# Replicape_B2.net
KiCad netlist of a schematic drawn in EAGLE
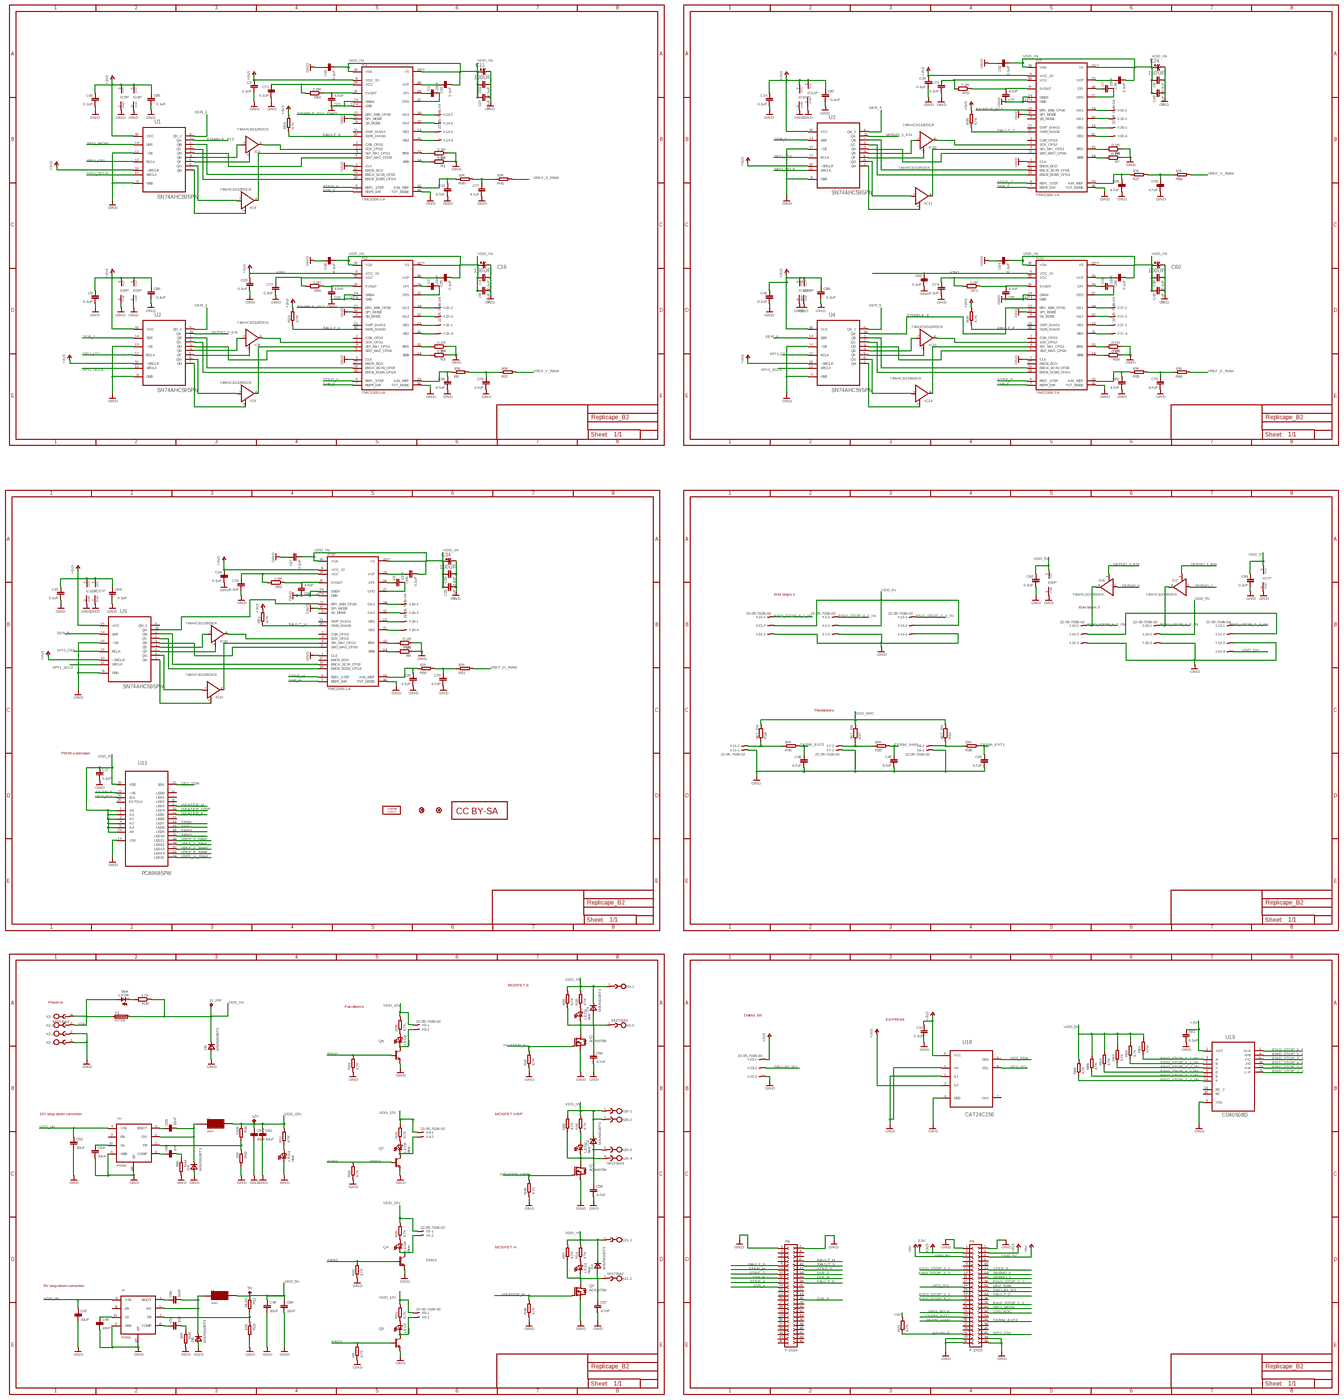
[diagram p0: schematic, sheet 1, overview]
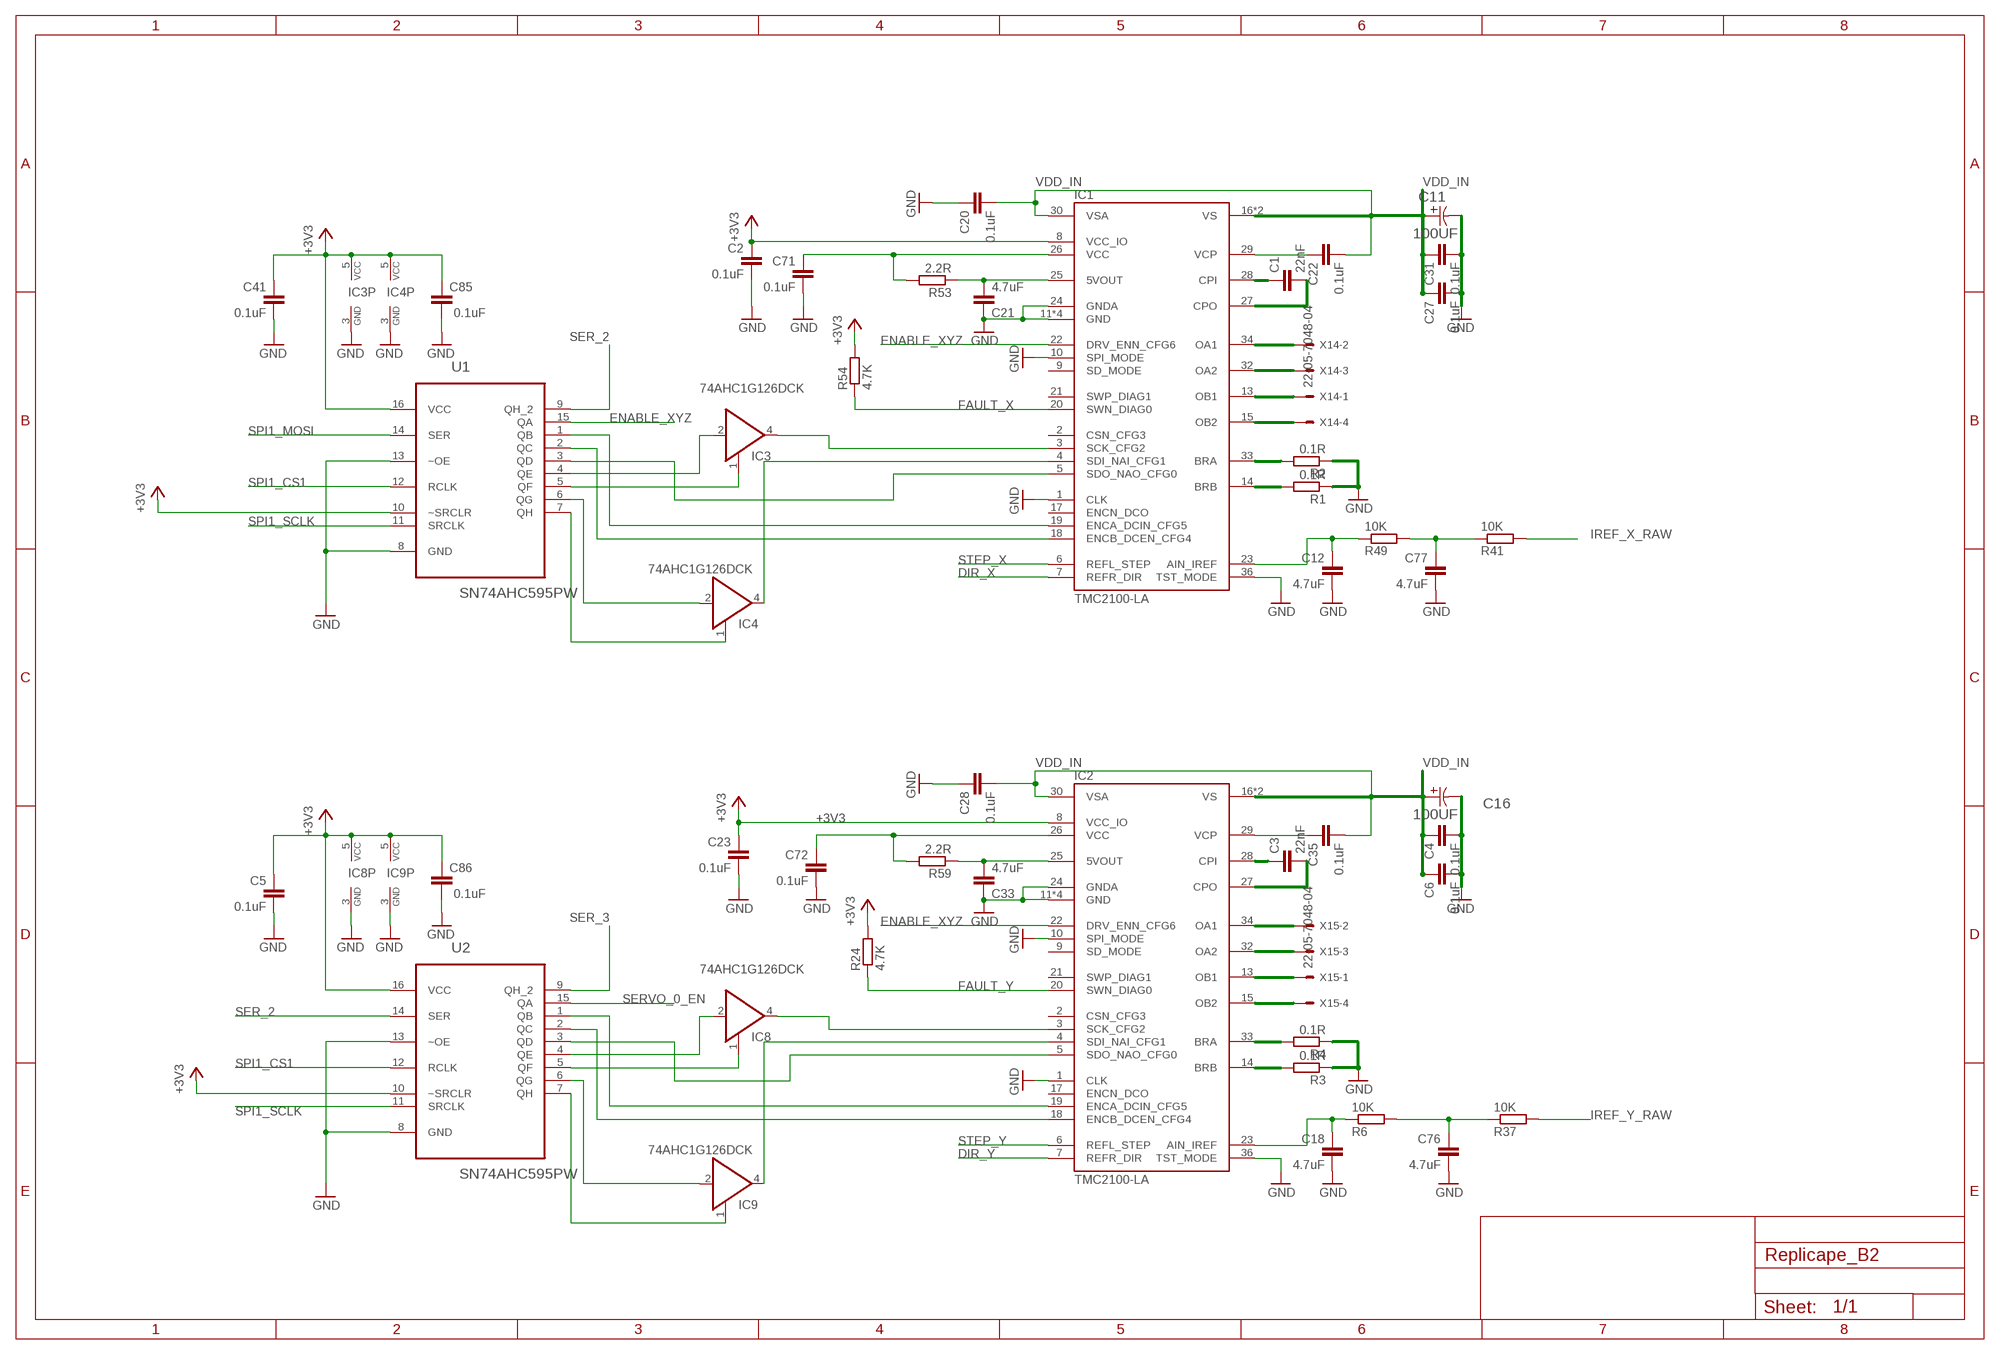
[diagram p1: schematic, sheet 1, part 1 of 4]
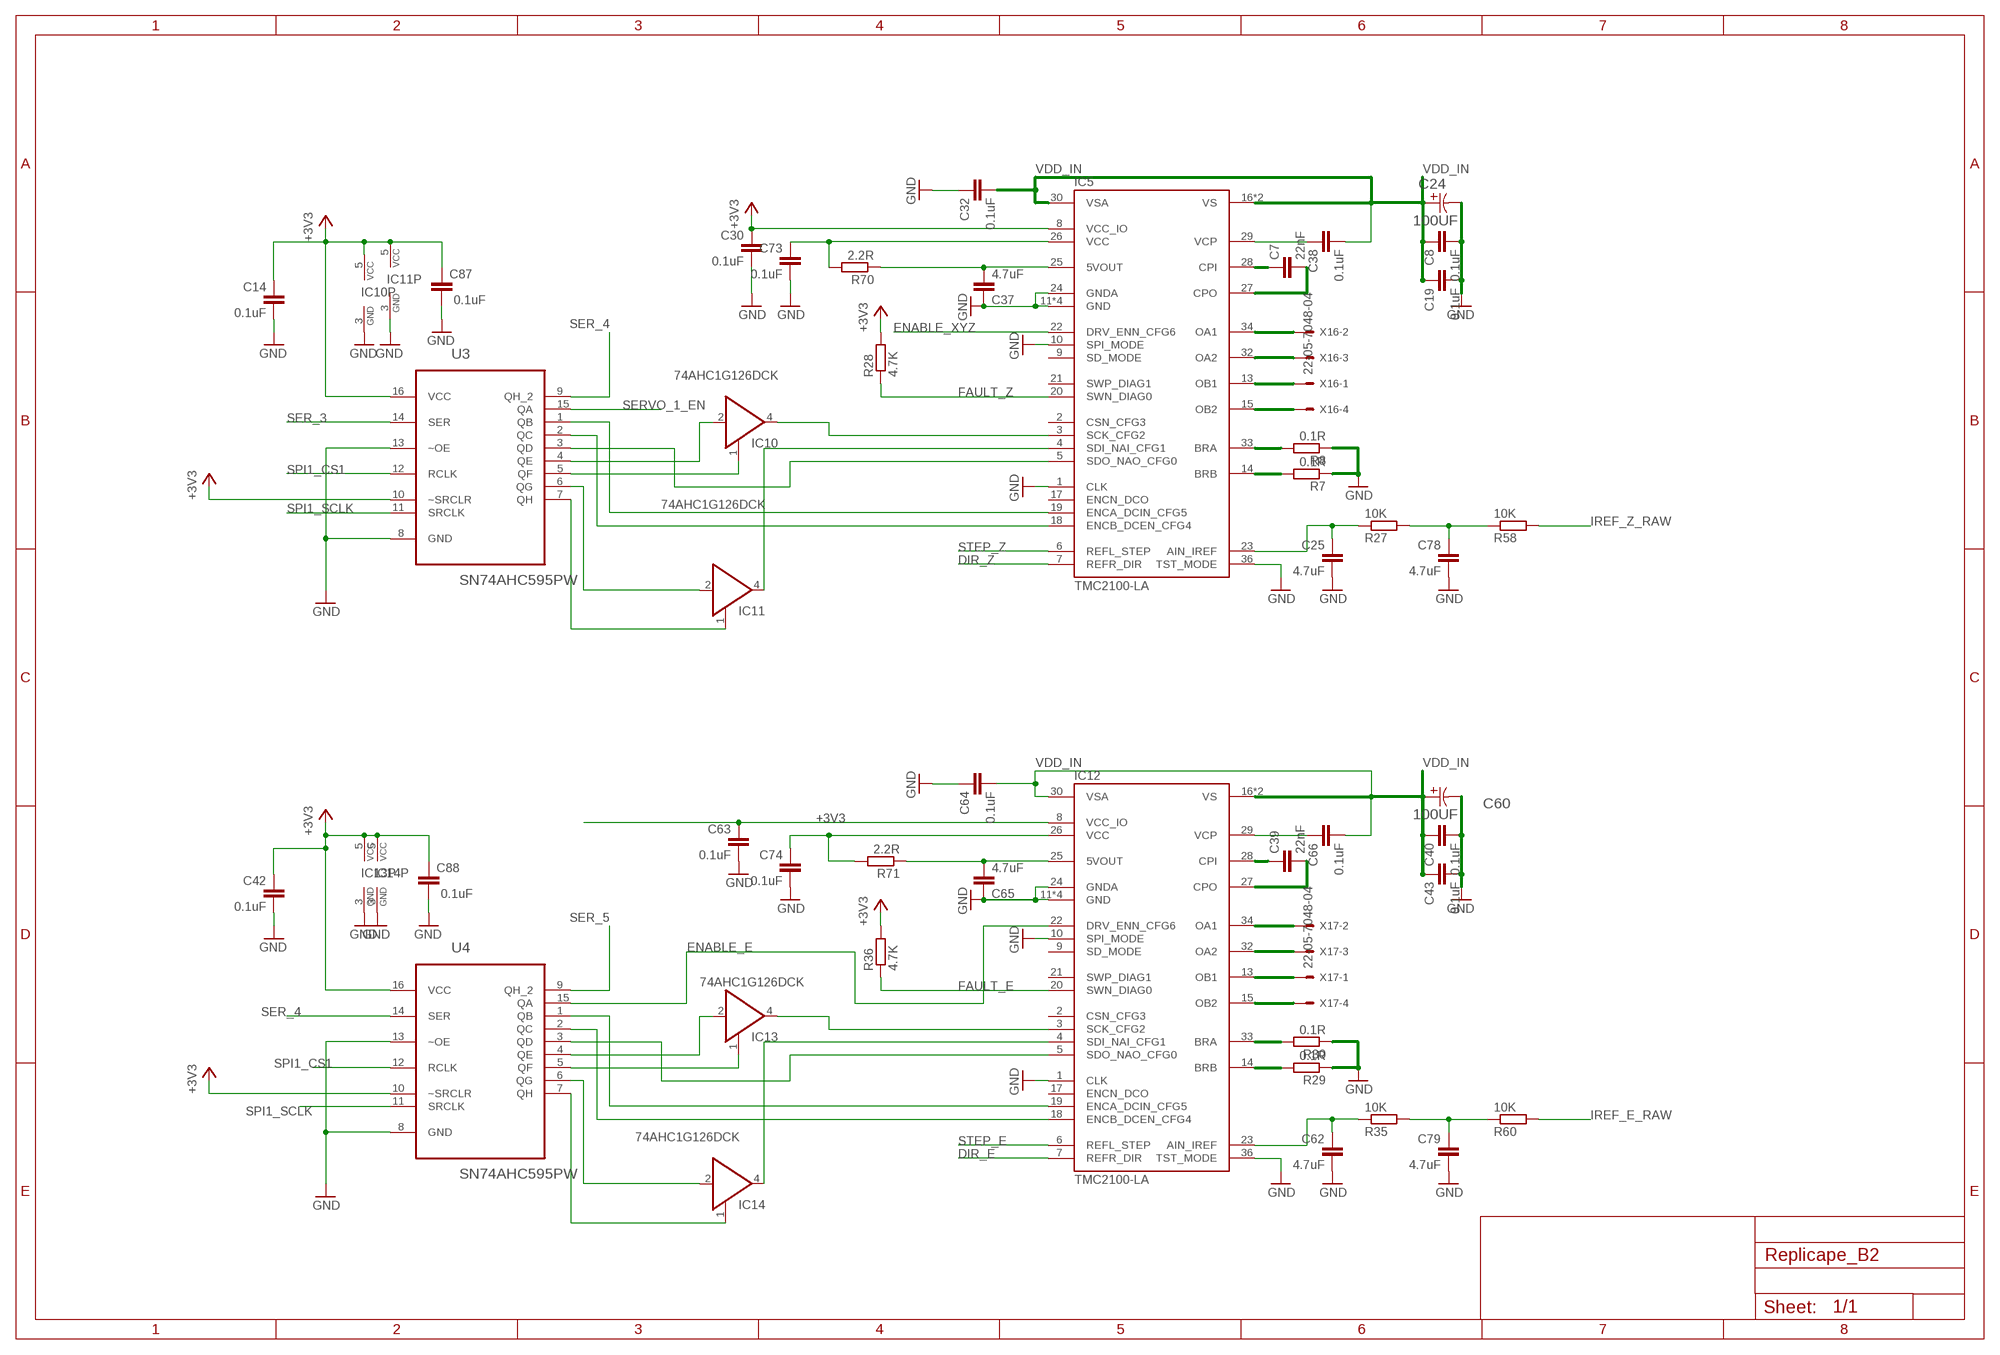
[diagram p2: schematic, sheet 1, part 2 of 4]
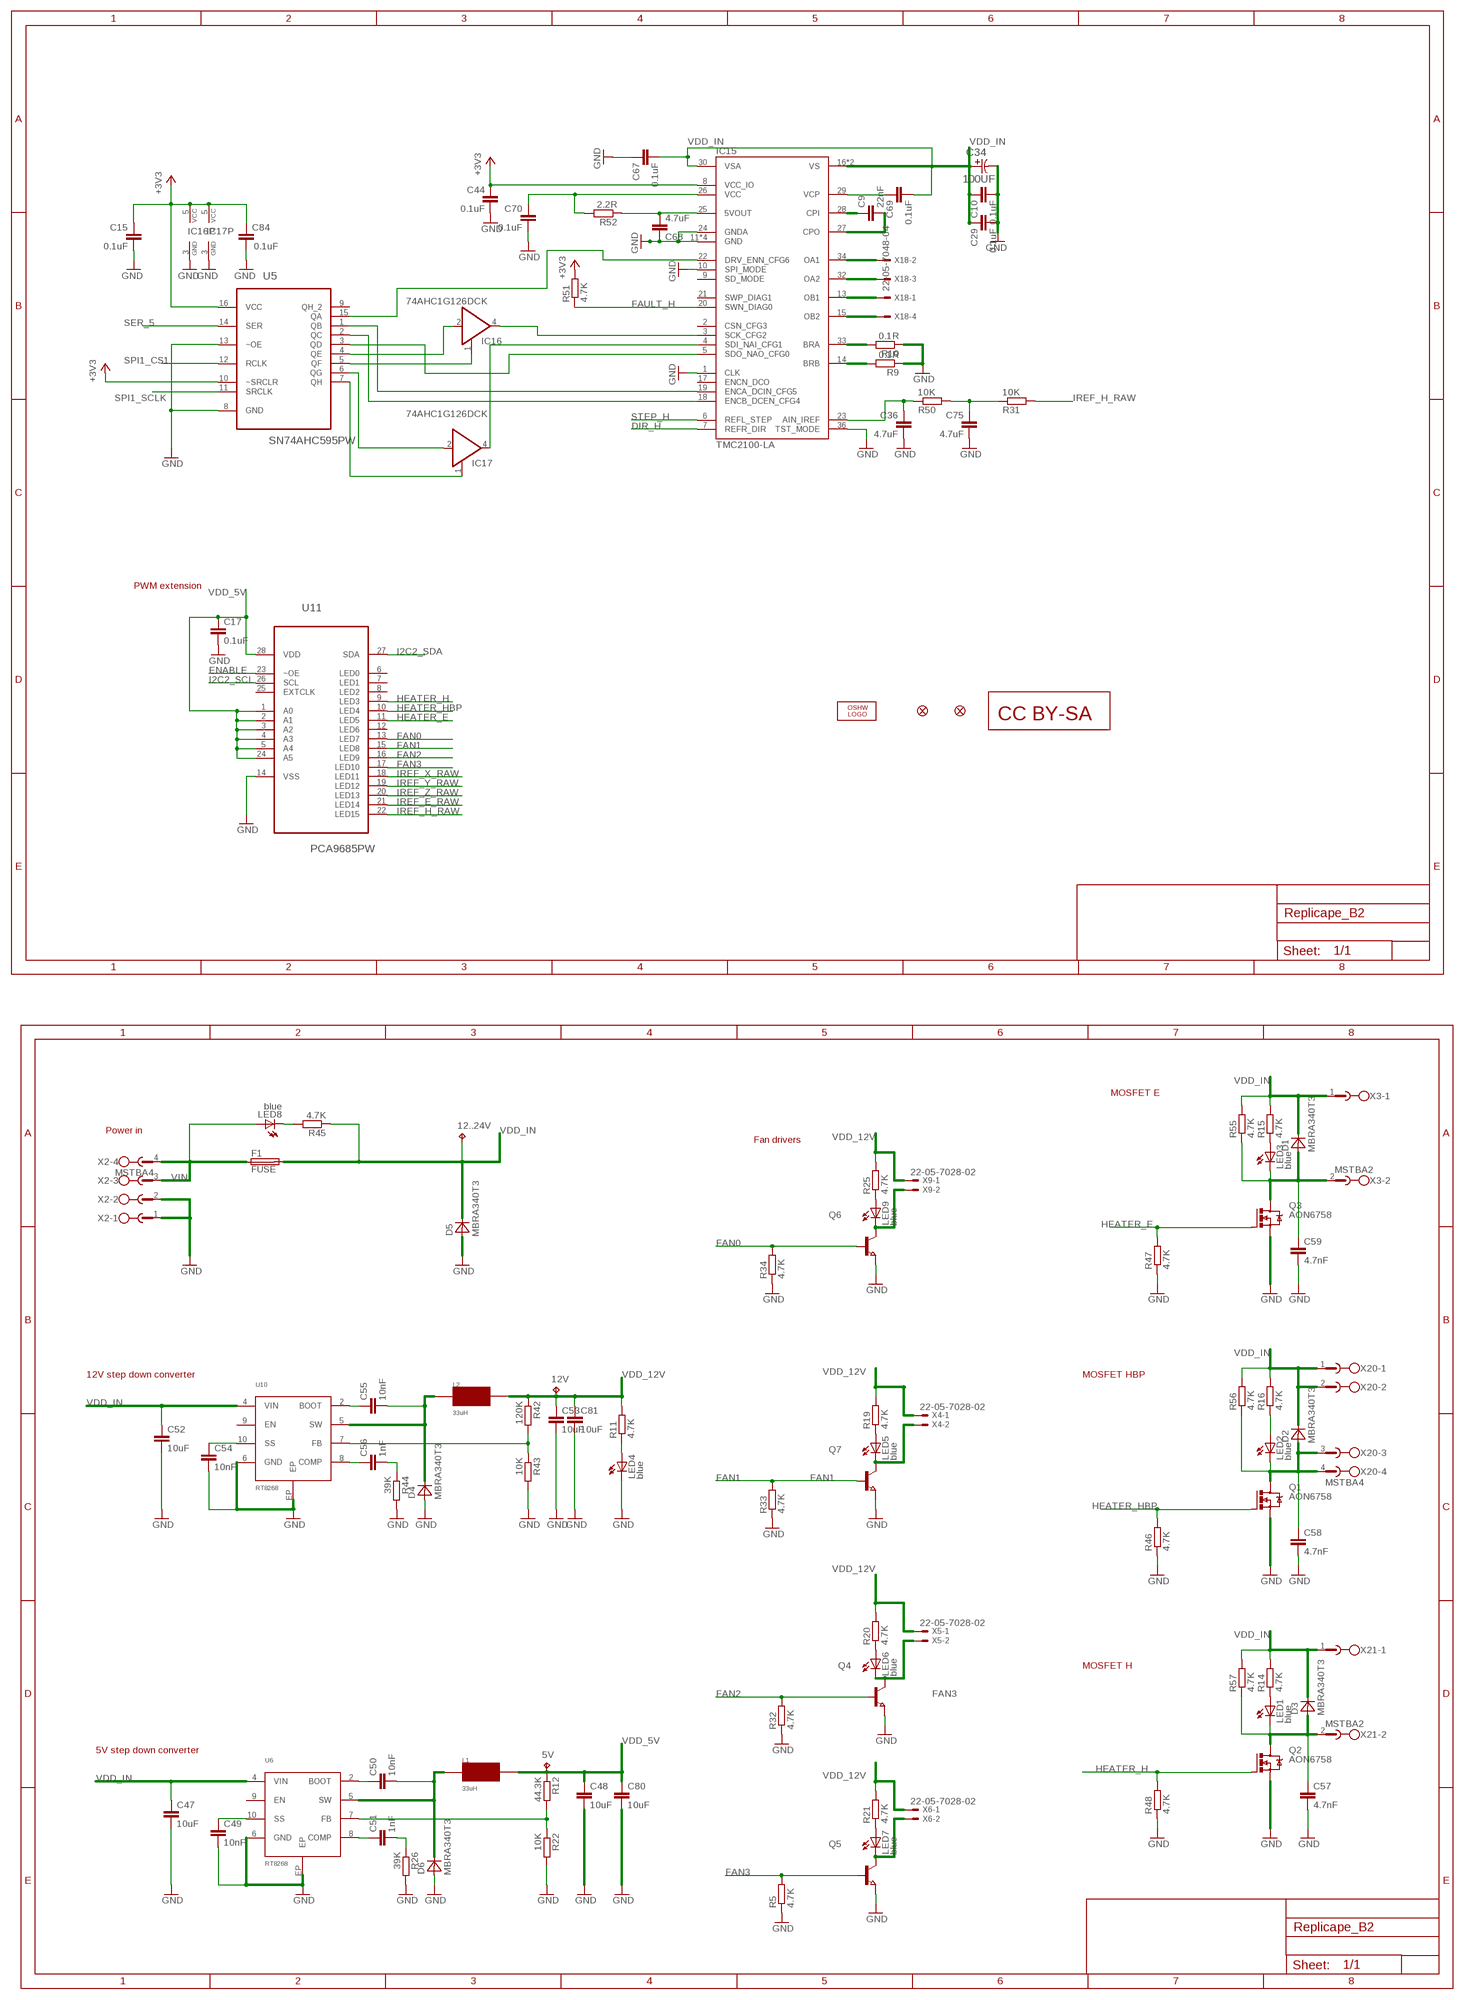
[diagram p3: schematic, sheet 1, part 3 of 4]
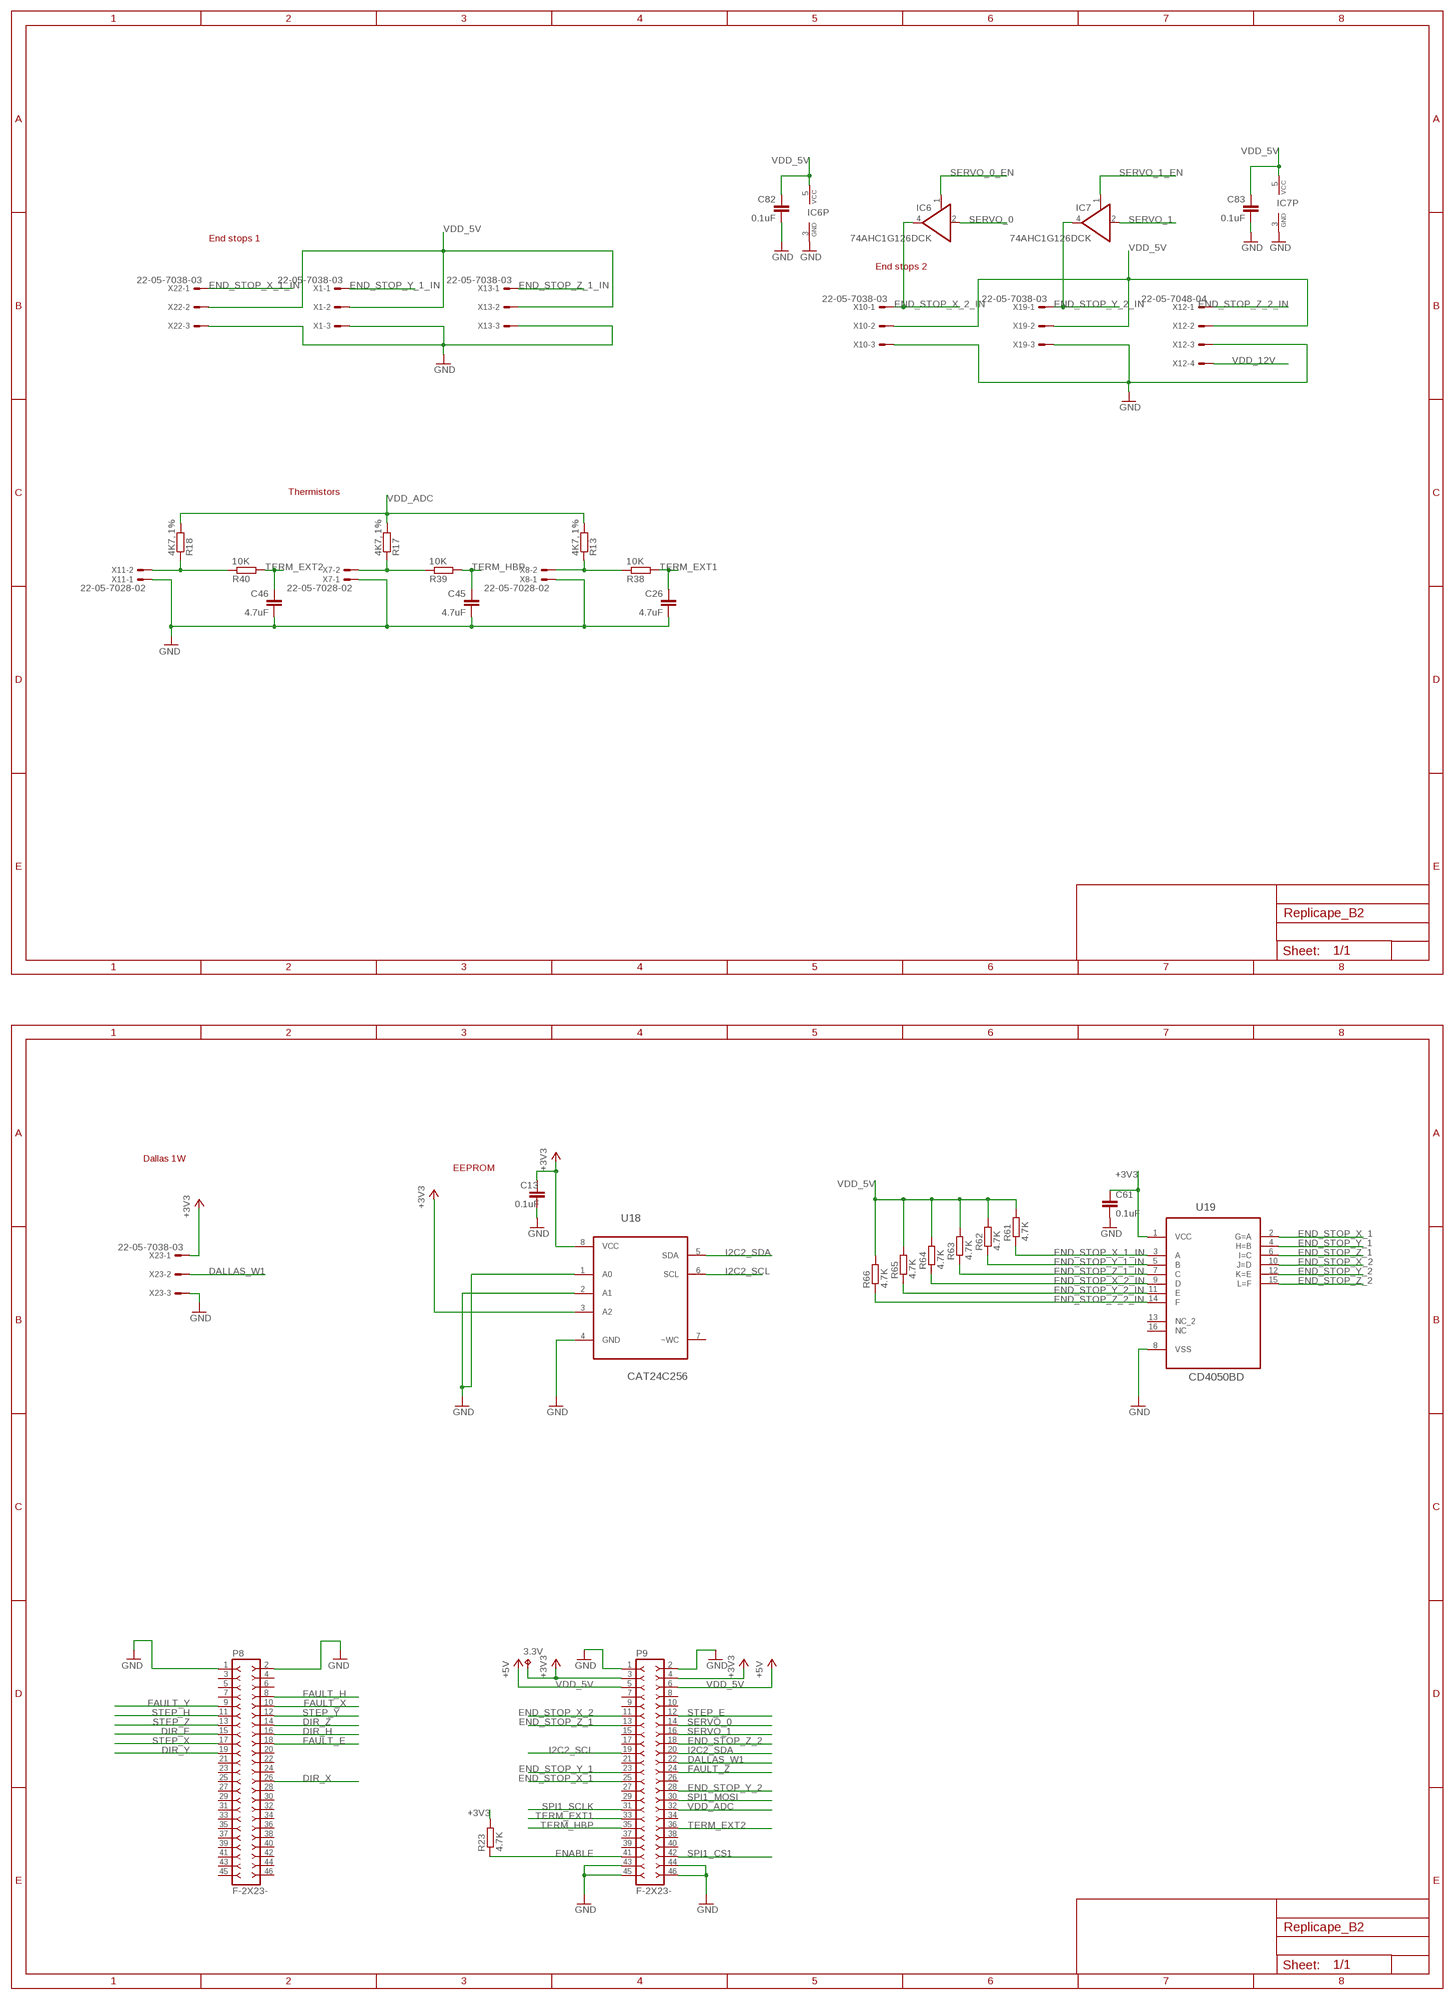
[diagram p4: schematic, sheet 1, part 4 of 4]

(export (version "E")
  (design (tool "Eeschema 10.0.6"))
  (components
    (comp (ref "3.3V")
      (value "TPB1,27")
      (footprint "eagle-import:B1,27")
      (libsource (lib "eagle-import") (part "TPB1,27"))
    )
    (comp (ref "5V")
      (value "TPB1,27")
      (footprint "eagle-import:B1,27")
      (libsource (lib "eagle-import") (part "TPB1,27"))
    )
    (comp (ref "12..24V")
      (value "TPB1,27")
      (footprint "eagle-import:B1,27")
      (libsource (lib "eagle-import") (part "TPB1,27"))
    )
    (comp (ref "12V")
      (value "TPB1,27")
      (footprint "eagle-import:B1,27")
      (libsource (lib "eagle-import") (part "TPB1,27"))
    )
    (comp (ref "C1")
      (value "22nF")
      (footprint "eagle-import:C0402")
      (libsource (lib "eagle-import") (part "C-EUC0402"))
    )
    (comp (ref "C2")
      (value "0.1uF")
      (footprint "eagle-import:C0402")
      (libsource (lib "eagle-import") (part "C-EUC0402"))
    )
    (comp (ref "C3")
      (value "22nF")
      (footprint "eagle-import:C0402")
      (libsource (lib "eagle-import") (part "C-EUC0402"))
    )
    (comp (ref "C4")
      (value "0.1uF")
      (footprint "eagle-import:C0402")
      (libsource (lib "eagle-import") (part "C-EUC0402"))
    )
    (comp (ref "C5")
      (value "0.1uF")
      (footprint "eagle-import:C0402")
      (libsource (lib "eagle-import") (part "C-EUC0402"))
    )
    (comp (ref "C6")
      (value "0.1uF")
      (footprint "eagle-import:C0402")
      (libsource (lib "eagle-import") (part "C-EUC0402"))
    )
    (comp (ref "C7")
      (value "22nF")
      (footprint "eagle-import:C0402")
      (libsource (lib "eagle-import") (part "C-EUC0402"))
    )
    (comp (ref "C8")
      (value "0.1uF")
      (footprint "eagle-import:C0402")
      (libsource (lib "eagle-import") (part "C-EUC0402"))
    )
    (comp (ref "C9")
      (value "22nF")
      (footprint "eagle-import:C0402")
      (libsource (lib "eagle-import") (part "C-EUC0402"))
    )
    (comp (ref "C10")
      (value "0.1uF")
      (footprint "eagle-import:C0402")
      (libsource (lib "eagle-import") (part "C-EUC0402"))
    )
    (comp (ref "C11")
      (value "100UF")
      (footprint "eagle-import:CAPAE660X800N")
      (fields (field (name "MPN") "EEE-FK1V101XP") (field (name "TOLERANCE") "±20 %"))
      (libsource (lib "eagle-import") (part "EEE--CASE-D8FK1V101XP"))
    )
    (comp (ref "C12")
      (value "4.7uF")
      (footprint "eagle-import:C0402")
      (libsource (lib "eagle-import") (part "C-EUC0402"))
    )
    (comp (ref "C13")
      (value "0.1uF")
      (footprint "eagle-import:C0402")
      (libsource (lib "eagle-import") (part "C-EUC0402"))
    )
    (comp (ref "C14")
      (value "0.1uF")
      (footprint "eagle-import:C0402")
      (libsource (lib "eagle-import") (part "C-EUC0402"))
    )
    (comp (ref "C15")
      (value "0.1uF")
      (footprint "eagle-import:C0402")
      (libsource (lib "eagle-import") (part "C-EUC0402"))
    )
    (comp (ref "C16")
      (value "100UF")
      (footprint "eagle-import:CAPAE660X800N")
      (fields (field (name "MPN") "EEE-FK1V101XP") (field (name "TOLERANCE") "±20 %"))
      (libsource (lib "eagle-import") (part "EEE--CASE-D8FK1V101XP"))
    )
    (comp (ref "C17")
      (value "0.1uF")
      (footprint "eagle-import:C0402")
      (libsource (lib "eagle-import") (part "C-EUC0402"))
    )
    (comp (ref "C18")
      (value "4.7uF")
      (footprint "eagle-import:C0402")
      (libsource (lib "eagle-import") (part "C-EUC0402"))
    )
    (comp (ref "C19")
      (value "0.1uF")
      (footprint "eagle-import:C0402")
      (libsource (lib "eagle-import") (part "C-EUC0402"))
    )
    (comp (ref "C20")
      (value "0.1uF")
      (footprint "eagle-import:C0402")
      (libsource (lib "eagle-import") (part "C-EUC0402"))
    )
    (comp (ref "C21")
      (value "4.7uF")
      (footprint "eagle-import:C0402")
      (libsource (lib "eagle-import") (part "C-EUC0402"))
    )
    (comp (ref "C22")
      (value "0.1uF")
      (footprint "eagle-import:C0402")
      (libsource (lib "eagle-import") (part "C-EUC0402"))
    )
    (comp (ref "C23")
      (value "0.1uF")
      (footprint "eagle-import:C0402")
      (libsource (lib "eagle-import") (part "C-EUC0402"))
    )
    (comp (ref "C24")
      (value "100UF")
      (footprint "eagle-import:CAPAE660X800N")
      (fields (field (name "MPN") "EEE-FK1V101XP") (field (name "TOLERANCE") "±20 %"))
      (libsource (lib "eagle-import") (part "EEE--CASE-D8FK1V101XP"))
    )
    (comp (ref "C25")
      (value "4.7uF")
      (footprint "eagle-import:C0402")
      (libsource (lib "eagle-import") (part "C-EUC0402"))
    )
    (comp (ref "C26")
      (value "4.7uF")
      (footprint "eagle-import:C0402")
      (libsource (lib "eagle-import") (part "C-EUC0402"))
    )
    (comp (ref "C27")
      (value "0.1uF")
      (footprint "eagle-import:C0402")
      (libsource (lib "eagle-import") (part "C-EUC0402"))
    )
    (comp (ref "C28")
      (value "0.1uF")
      (footprint "eagle-import:C0402")
      (libsource (lib "eagle-import") (part "C-EUC0402"))
    )
    (comp (ref "C29")
      (value "0.1uF")
      (footprint "eagle-import:C0402")
      (libsource (lib "eagle-import") (part "C-EUC0402"))
    )
    (comp (ref "C30")
      (value "0.1uF")
      (footprint "eagle-import:C0402")
      (libsource (lib "eagle-import") (part "C-EUC0402"))
    )
    (comp (ref "C31")
      (value "0.1uF")
      (footprint "eagle-import:C0402")
      (libsource (lib "eagle-import") (part "C-EUC0402"))
    )
    (comp (ref "C32")
      (value "0.1uF")
      (footprint "eagle-import:C0402")
      (libsource (lib "eagle-import") (part "C-EUC0402"))
    )
    (comp (ref "C33")
      (value "4.7uF")
      (footprint "eagle-import:C0402")
      (libsource (lib "eagle-import") (part "C-EUC0402"))
    )
    (comp (ref "C34")
      (value "100UF")
      (footprint "eagle-import:CAPAE660X800N")
      (fields (field (name "MPN") "EEE-FK1V101XP") (field (name "TOLERANCE") "±20 %"))
      (libsource (lib "eagle-import") (part "EEE--CASE-D8FK1V101XP"))
    )
    (comp (ref "C35")
      (value "0.1uF")
      (footprint "eagle-import:C0402")
      (libsource (lib "eagle-import") (part "C-EUC0402"))
    )
    (comp (ref "C36")
      (value "4.7uF")
      (footprint "eagle-import:C0402")
      (libsource (lib "eagle-import") (part "C-EUC0402"))
    )
    (comp (ref "C37")
      (value "4.7uF")
      (footprint "eagle-import:C0402")
      (libsource (lib "eagle-import") (part "C-EUC0402"))
    )
    (comp (ref "C38")
      (value "0.1uF")
      (footprint "eagle-import:C0402")
      (libsource (lib "eagle-import") (part "C-EUC0402"))
    )
    (comp (ref "C39")
      (value "22nF")
      (footprint "eagle-import:C0402")
      (libsource (lib "eagle-import") (part "C-EUC0402"))
    )
    (comp (ref "C40")
      (value "0.1uF")
      (footprint "eagle-import:C0402")
      (libsource (lib "eagle-import") (part "C-EUC0402"))
    )
    (comp (ref "C41")
      (value "0.1uF")
      (footprint "eagle-import:C0402")
      (libsource (lib "eagle-import") (part "C-EUC0402"))
    )
    (comp (ref "C42")
      (value "0.1uF")
      (footprint "eagle-import:C0402")
      (libsource (lib "eagle-import") (part "C-EUC0402"))
    )
    (comp (ref "C43")
      (value "0.1uF")
      (footprint "eagle-import:C0402")
      (libsource (lib "eagle-import") (part "C-EUC0402"))
    )
    (comp (ref "C44")
      (value "0.1uF")
      (footprint "eagle-import:C0402")
      (libsource (lib "eagle-import") (part "C-EUC0402"))
    )
    (comp (ref "C45")
      (value "4.7uF")
      (footprint "eagle-import:C0402")
      (libsource (lib "eagle-import") (part "C-EUC0402"))
    )
    (comp (ref "C46")
      (value "4.7uF")
      (footprint "eagle-import:C0402")
      (libsource (lib "eagle-import") (part "C-EUC0402"))
    )
    (comp (ref "C47")
      (value "10uF")
      (footprint "eagle-import:C1206")
      (libsource (lib "eagle-import") (part "C-EUC1206"))
    )
    (comp (ref "C48")
      (value "10uF")
      (footprint "eagle-import:C1206")
      (libsource (lib "eagle-import") (part "C-EUC1206"))
    )
    (comp (ref "C49")
      (value "10nF")
      (footprint "eagle-import:C0402")
      (libsource (lib "eagle-import") (part "C-EUC0402"))
    )
    (comp (ref "C50")
      (value "10nF")
      (footprint "eagle-import:C0402")
      (libsource (lib "eagle-import") (part "C-EUC0402"))
    )
    (comp (ref "C51")
      (value "1nF")
      (footprint "eagle-import:C0402")
      (libsource (lib "eagle-import") (part "C-EUC0402"))
    )
    (comp (ref "C52")
      (value "10uF")
      (footprint "eagle-import:C1206")
      (libsource (lib "eagle-import") (part "C-EUC1206"))
    )
    (comp (ref "C53")
      (value "10uF")
      (footprint "eagle-import:C1206")
      (libsource (lib "eagle-import") (part "C-EUC1206"))
    )
    (comp (ref "C54")
      (value "10nF")
      (footprint "eagle-import:C0402")
      (libsource (lib "eagle-import") (part "C-EUC0402"))
    )
    (comp (ref "C55")
      (value "10nF")
      (footprint "eagle-import:C0402")
      (libsource (lib "eagle-import") (part "C-EUC0402"))
    )
    (comp (ref "C56")
      (value "1nF")
      (footprint "eagle-import:C0402")
      (libsource (lib "eagle-import") (part "C-EUC0402"))
    )
    (comp (ref "C57")
      (value "4.7nF")
      (footprint "eagle-import:C0402")
      (libsource (lib "eagle-import") (part "C-EUC0402"))
    )
    (comp (ref "C58")
      (value "4.7nF")
      (footprint "eagle-import:C0402")
      (libsource (lib "eagle-import") (part "C-EUC0402"))
    )
    (comp (ref "C59")
      (value "4.7nF")
      (footprint "eagle-import:C0402")
      (libsource (lib "eagle-import") (part "C-EUC0402"))
    )
    (comp (ref "C60")
      (value "100UF")
      (footprint "eagle-import:CAPAE660X800N")
      (fields (field (name "MPN") "EEE-FK1V101XP") (field (name "TOLERANCE") "±20 %"))
      (libsource (lib "eagle-import") (part "EEE--CASE-D8FK1V101XP"))
    )
    (comp (ref "C61")
      (value "0.1uF")
      (footprint "eagle-import:C0402")
      (libsource (lib "eagle-import") (part "C-EUC0402"))
    )
    (comp (ref "C62")
      (value "4.7uF")
      (footprint "eagle-import:C0402")
      (libsource (lib "eagle-import") (part "C-EUC0402"))
    )
    (comp (ref "C63")
      (value "0.1uF")
      (footprint "eagle-import:C0402")
      (libsource (lib "eagle-import") (part "C-EUC0402"))
    )
    (comp (ref "C64")
      (value "0.1uF")
      (footprint "eagle-import:C0402")
      (libsource (lib "eagle-import") (part "C-EUC0402"))
    )
    (comp (ref "C65")
      (value "4.7uF")
      (footprint "eagle-import:C0402")
      (libsource (lib "eagle-import") (part "C-EUC0402"))
    )
    (comp (ref "C66")
      (value "0.1uF")
      (footprint "eagle-import:C0402")
      (libsource (lib "eagle-import") (part "C-EUC0402"))
    )
    (comp (ref "C67")
      (value "0.1uF")
      (footprint "eagle-import:C0402")
      (libsource (lib "eagle-import") (part "C-EUC0402"))
    )
    (comp (ref "C68")
      (value "4.7uF")
      (footprint "eagle-import:C0402")
      (libsource (lib "eagle-import") (part "C-EUC0402"))
    )
    (comp (ref "C69")
      (value "0.1uF")
      (footprint "eagle-import:C0402")
      (libsource (lib "eagle-import") (part "C-EUC0402"))
    )
    (comp (ref "C70")
      (value "0.1uF")
      (footprint "eagle-import:C0402")
      (libsource (lib "eagle-import") (part "C-EUC0402"))
    )
    (comp (ref "C71")
      (value "0.1uF")
      (footprint "eagle-import:C0402")
      (libsource (lib "eagle-import") (part "C-EUC0402"))
    )
    (comp (ref "C72")
      (value "0.1uF")
      (footprint "eagle-import:C0402")
      (libsource (lib "eagle-import") (part "C-EUC0402"))
    )
    (comp (ref "C73")
      (value "0.1uF")
      (footprint "eagle-import:C0402")
      (libsource (lib "eagle-import") (part "C-EUC0402"))
    )
    (comp (ref "C74")
      (value "0.1uF")
      (footprint "eagle-import:C0402")
      (libsource (lib "eagle-import") (part "C-EUC0402"))
    )
    (comp (ref "C75")
      (value "4.7uF")
      (footprint "eagle-import:C0402")
      (libsource (lib "eagle-import") (part "C-EUC0402"))
    )
    (comp (ref "C76")
      (value "4.7uF")
      (footprint "eagle-import:C0402")
      (libsource (lib "eagle-import") (part "C-EUC0402"))
    )
    (comp (ref "C77")
      (value "4.7uF")
      (footprint "eagle-import:C0402")
      (libsource (lib "eagle-import") (part "C-EUC0402"))
    )
    (comp (ref "C78")
      (value "4.7uF")
      (footprint "eagle-import:C0402")
      (libsource (lib "eagle-import") (part "C-EUC0402"))
    )
    (comp (ref "C79")
      (value "4.7uF")
      (footprint "eagle-import:C0402")
      (libsource (lib "eagle-import") (part "C-EUC0402"))
    )
    (comp (ref "C80")
      (value "10uF")
      (footprint "eagle-import:C1206")
      (libsource (lib "eagle-import") (part "C-EUC1206"))
    )
    (comp (ref "C81")
      (value "10uF")
      (footprint "eagle-import:C1206")
      (libsource (lib "eagle-import") (part "C-EUC1206"))
    )
    (comp (ref "C82")
      (value "0.1uF")
      (footprint "eagle-import:C0402")
      (libsource (lib "eagle-import") (part "C-EUC0402"))
    )
    (comp (ref "C83")
      (value "0.1uF")
      (footprint "eagle-import:C0402")
      (libsource (lib "eagle-import") (part "C-EUC0402"))
    )
    (comp (ref "C84")
      (value "0.1uF")
      (footprint "eagle-import:C0402")
      (libsource (lib "eagle-import") (part "C-EUC0402"))
    )
    (comp (ref "C85")
      (value "0.1uF")
      (footprint "eagle-import:C0402")
      (libsource (lib "eagle-import") (part "C-EUC0402"))
    )
    (comp (ref "C86")
      (value "0.1uF")
      (footprint "eagle-import:C0402")
      (libsource (lib "eagle-import") (part "C-EUC0402"))
    )
    (comp (ref "C87")
      (value "0.1uF")
      (footprint "eagle-import:C0402")
      (libsource (lib "eagle-import") (part "C-EUC0402"))
    )
    (comp (ref "C88")
      (value "0.1uF")
      (footprint "eagle-import:C0402")
      (libsource (lib "eagle-import") (part "C-EUC0402"))
    )
    (comp (ref "D1")
      (value "MBRA340T3")
      (footprint "eagle-import:SMA")
      (libsource (lib "eagle-import") (part "MBRA340T3"))
    )
    (comp (ref "D2")
      (value "MBRA340T3")
      (footprint "eagle-import:SMA")
      (libsource (lib "eagle-import") (part "MBRA340T3"))
    )
    (comp (ref "D3")
      (value "MBRA340T3")
      (footprint "eagle-import:SMA")
      (libsource (lib "eagle-import") (part "MBRA340T3"))
    )
    (comp (ref "D4")
      (value "MBRA340T3")
      (footprint "eagle-import:SMA")
      (libsource (lib "eagle-import") (part "MBRA340T3"))
    )
    (comp (ref "D5")
      (value "MBRA340T3")
      (footprint "eagle-import:SMA")
      (libsource (lib "eagle-import") (part "MBRA340T3"))
    )
    (comp (ref "D6")
      (value "MBRA340T3")
      (footprint "eagle-import:SMA")
      (libsource (lib "eagle-import") (part "MBRA340T3"))
    )
    (comp (ref "F1")
      (value "FUSE")
      (footprint "eagle-import:3557")
      (libsource (lib "eagle-import") (part "FUSE"))
    )
    (comp (ref "IC1")
      (value "TMC2100-LA")
      (footprint "eagle-import:QFN36-PAD")
      (libsource (lib "eagle-import") (part "TMC2100-LA"))
    )
    (comp (ref "IC2")
      (value "TMC2100-LA")
      (footprint "eagle-import:QFN36-PAD")
      (libsource (lib "eagle-import") (part "TMC2100-LA"))
    )
    (comp (ref "IC3")
      (value "74AHC1G126DCK")
      (footprint "eagle-import:SC70-5")
      (libsource (lib "eagle-import") (part "741G126DCKAHC"))
    )
    (comp (ref "IC4")
      (value "74AHC1G126DCK")
      (footprint "eagle-import:SC70-5")
      (libsource (lib "eagle-import") (part "741G126DCKAHC"))
    )
    (comp (ref "IC5")
      (value "TMC2100-LA")
      (footprint "eagle-import:QFN36-PAD")
      (libsource (lib "eagle-import") (part "TMC2100-LA"))
    )
    (comp (ref "IC6")
      (value "74AHC1G126DCK")
      (footprint "eagle-import:SC70-5")
      (libsource (lib "eagle-import") (part "741G126DCKAHC"))
    )
    (comp (ref "IC7")
      (value "74AHC1G126DCK")
      (footprint "eagle-import:SC70-5")
      (libsource (lib "eagle-import") (part "741G126DCKAHC"))
    )
    (comp (ref "IC8")
      (value "74AHC1G126DCK")
      (footprint "eagle-import:SC70-5")
      (libsource (lib "eagle-import") (part "741G126DCKAHC"))
    )
    (comp (ref "IC9")
      (value "74AHC1G126DCK")
      (footprint "eagle-import:SC70-5")
      (libsource (lib "eagle-import") (part "741G126DCKAHC"))
    )
    (comp (ref "IC10")
      (value "74AHC1G126DCK")
      (footprint "eagle-import:SC70-5")
      (libsource (lib "eagle-import") (part "741G126DCKAHC"))
    )
    (comp (ref "IC11")
      (value "74AHC1G126DCK")
      (footprint "eagle-import:SC70-5")
      (libsource (lib "eagle-import") (part "741G126DCKAHC"))
    )
    (comp (ref "IC12")
      (value "TMC2100-LA")
      (footprint "eagle-import:QFN36-PAD")
      (libsource (lib "eagle-import") (part "TMC2100-LA"))
    )
    (comp (ref "IC13")
      (value "74AHC1G126DCK")
      (footprint "eagle-import:SC70-5")
      (libsource (lib "eagle-import") (part "741G126DCKAHC"))
    )
    (comp (ref "IC14")
      (value "74AHC1G126DCK")
      (footprint "eagle-import:SC70-5")
      (libsource (lib "eagle-import") (part "741G126DCKAHC"))
    )
    (comp (ref "IC15")
      (value "TMC2100-LA")
      (footprint "eagle-import:QFN36-PAD")
      (libsource (lib "eagle-import") (part "TMC2100-LA"))
    )
    (comp (ref "IC16")
      (value "74AHC1G126DCK")
      (footprint "eagle-import:SC70-5")
      (libsource (lib "eagle-import") (part "741G126DCKAHC"))
    )
    (comp (ref "IC17")
      (value "74AHC1G126DCK")
      (footprint "eagle-import:SC70-5")
      (libsource (lib "eagle-import") (part "741G126DCKAHC"))
    )
    (comp (ref "JP1")
      (value "FIDUCIAL1X2.5")
      (footprint "eagle-import:FIDUCIAL-1X2.5")
      (libsource (lib "eagle-import") (part "FIDUCIAL1X2.5"))
    )
    (comp (ref "JP2")
      (value "FIDUCIAL1X2.5")
      (footprint "eagle-import:FIDUCIAL-1X2.5")
      (libsource (lib "eagle-import") (part "FIDUCIAL1X2.5"))
    )
    (comp (ref "L1")
      (value "33uH")
      (footprint "eagle-import:NR8040T330")
      (libsource (lib "eagle-import") (part "RT8040T330"))
    )
    (comp (ref "L2")
      (value "33uH")
      (footprint "eagle-import:NR8040T330")
      (libsource (lib "eagle-import") (part "RT8040T330"))
    )
    (comp (ref "LED1")
      (value "blue")
      (footprint "eagle-import:CHIP-LED0603")
      (libsource (lib "eagle-import") (part "LEDCHIP-LED0603"))
    )
    (comp (ref "LED2")
      (value "blue")
      (footprint "eagle-import:CHIP-LED0603")
      (libsource (lib "eagle-import") (part "LEDCHIP-LED0603"))
    )
    (comp (ref "LED3")
      (value "blue")
      (footprint "eagle-import:CHIP-LED0603")
      (libsource (lib "eagle-import") (part "LEDCHIP-LED0603"))
    )
    (comp (ref "LED4")
      (value "blue")
      (footprint "eagle-import:CHIP-LED0603")
      (libsource (lib "eagle-import") (part "LEDCHIP-LED0603"))
    )
    (comp (ref "LED5")
      (value "blue")
      (footprint "eagle-import:CHIP-LED0603")
      (libsource (lib "eagle-import") (part "LEDCHIP-LED0603"))
    )
    (comp (ref "LED6")
      (value "blue")
      (footprint "eagle-import:CHIP-LED0603")
      (libsource (lib "eagle-import") (part "LEDCHIP-LED0603"))
    )
    (comp (ref "LED7")
      (value "blue")
      (footprint "eagle-import:CHIP-LED0603")
      (libsource (lib "eagle-import") (part "LEDCHIP-LED0603"))
    )
    (comp (ref "LED8")
      (value "blue")
      (footprint "eagle-import:CHIP-LED0603")
      (libsource (lib "eagle-import") (part "LEDCHIP-LED0603"))
    )
    (comp (ref "LED9")
      (value "blue")
      (footprint "eagle-import:CHIP-LED0603")
      (libsource (lib "eagle-import") (part "LEDCHIP-LED0603"))
    )
    (comp (ref "LOGO1")
      (value "OSHW_LOGO_FILLX0200-NT")
      (footprint "eagle-import:OSHW_FILLX200_NOTEXT")
      (libsource (lib "eagle-import") (part "OSHW_LOGO_FILLX0200-NT"))
    )
    (comp (ref "P8")
      (value "F-2X23-")
      (footprint "eagle-import:DIL-100-2X23")
      (libsource (lib "eagle-import") (part "F-2X23-"))
    )
    (comp (ref "P9")
      (value "F-2X23-")
      (footprint "eagle-import:DIL-100-2X23")
      (libsource (lib "eagle-import") (part "F-2X23-"))
    )
    (comp (ref "Q1")
      (value "AON6758")
      (footprint "eagle-import:8-DFN-EP-(5X6)")
      (libsource (lib "eagle-import") (part "AON6758"))
    )
    (comp (ref "Q2")
      (value "AON6758")
      (footprint "eagle-import:8-DFN-EP-(5X6)")
      (libsource (lib "eagle-import") (part "AON6758"))
    )
    (comp (ref "Q3")
      (value "AON6758")
      (footprint "eagle-import:8-DFN-EP-(5X6)")
      (libsource (lib "eagle-import") (part "AON6758"))
    )
    (comp (ref "Q4")
      (value "NPN-TRANSISTOR_SOT23")
      (footprint "eagle-import:SOT23")
      (libsource (lib "eagle-import") (part "NPN-TRANSISTOR_SOT23"))
    )
    (comp (ref "Q5")
      (value "NPN-TRANSISTOR_SOT23")
      (footprint "eagle-import:SOT23")
      (libsource (lib "eagle-import") (part "NPN-TRANSISTOR_SOT23"))
    )
    (comp (ref "Q6")
      (value "NPN-TRANSISTOR_SOT23")
      (footprint "eagle-import:SOT23")
      (libsource (lib "eagle-import") (part "NPN-TRANSISTOR_SOT23"))
    )
    (comp (ref "Q7")
      (value "NPN-TRANSISTOR_SOT23")
      (footprint "eagle-import:SOT23")
      (libsource (lib "eagle-import") (part "NPN-TRANSISTOR_SOT23"))
    )
    (comp (ref "R1")
      (value "0.1R")
      (footprint "eagle-import:R0805")
      (libsource (lib "eagle-import") (part "R-EU_R0805"))
    )
    (comp (ref "R2")
      (value "0.1R")
      (footprint "eagle-import:R0805")
      (libsource (lib "eagle-import") (part "R-EU_R0805"))
    )
    (comp (ref "R3")
      (value "0.1R")
      (footprint "eagle-import:R0805")
      (libsource (lib "eagle-import") (part "R-EU_R0805"))
    )
    (comp (ref "R4")
      (value "0.1R")
      (footprint "eagle-import:R0805")
      (libsource (lib "eagle-import") (part "R-EU_R0805"))
    )
    (comp (ref "R5")
      (value "4.7K")
      (footprint "eagle-import:R0402")
      (libsource (lib "eagle-import") (part "R-EU_R0402"))
    )
    (comp (ref "R6")
      (value "10K")
      (footprint "eagle-import:R0402")
      (libsource (lib "eagle-import") (part "R-EU_R0402"))
    )
    (comp (ref "R7")
      (value "0.1R")
      (footprint "eagle-import:R0805")
      (libsource (lib "eagle-import") (part "R-EU_R0805"))
    )
    (comp (ref "R8")
      (value "0.1R")
      (footprint "eagle-import:R0805")
      (libsource (lib "eagle-import") (part "R-EU_R0805"))
    )
    (comp (ref "R9")
      (value "0.1R")
      (footprint "eagle-import:R0805")
      (libsource (lib "eagle-import") (part "R-EU_R0805"))
    )
    (comp (ref "R10")
      (value "0.1R")
      (footprint "eagle-import:R0805")
      (libsource (lib "eagle-import") (part "R-EU_R0805"))
    )
    (comp (ref "R11")
      (value "4.7K")
      (footprint "eagle-import:R0402")
      (libsource (lib "eagle-import") (part "R-EU_R0402"))
    )
    (comp (ref "R12")
      (value "44.3K")
      (footprint "eagle-import:R0402")
      (libsource (lib "eagle-import") (part "R-EU_R0402"))
    )
    (comp (ref "R13")
      (value "4K7, 1%")
      (footprint "eagle-import:R0402")
      (libsource (lib "eagle-import") (part "R-EU_R0402"))
    )
    (comp (ref "R14")
      (value "4.7K")
      (footprint "eagle-import:R0402")
      (libsource (lib "eagle-import") (part "R-EU_R0402"))
    )
    (comp (ref "R15")
      (value "4.7K")
      (footprint "eagle-import:R0402")
      (libsource (lib "eagle-import") (part "R-EU_R0402"))
    )
    (comp (ref "R16")
      (value "4.7K")
      (footprint "eagle-import:R0402")
      (libsource (lib "eagle-import") (part "R-EU_R0402"))
    )
    (comp (ref "R17")
      (value "4K7, 1%")
      (footprint "eagle-import:R0402")
      (libsource (lib "eagle-import") (part "R-EU_R0402"))
    )
    (comp (ref "R18")
      (value "4K7, 1%")
      (footprint "eagle-import:R0402")
      (libsource (lib "eagle-import") (part "R-EU_R0402"))
    )
    (comp (ref "R19")
      (value "4.7K")
      (footprint "eagle-import:R0402")
      (libsource (lib "eagle-import") (part "R-EU_R0402"))
    )
    (comp (ref "R20")
      (value "4.7K")
      (footprint "eagle-import:R0402")
      (libsource (lib "eagle-import") (part "R-EU_R0402"))
    )
    (comp (ref "R21")
      (value "4.7K")
      (footprint "eagle-import:R0402")
      (libsource (lib "eagle-import") (part "R-EU_R0402"))
    )
    (comp (ref "R22")
      (value "10K")
      (footprint "eagle-import:R0402")
      (libsource (lib "eagle-import") (part "R-EU_R0402"))
    )
    (comp (ref "R23")
      (value "4.7K")
      (footprint "eagle-import:R0402")
      (libsource (lib "eagle-import") (part "R-EU_R0402"))
    )
    (comp (ref "R24")
      (value "4.7K")
      (footprint "eagle-import:R0402")
      (libsource (lib "eagle-import") (part "R-EU_R0402"))
    )
    (comp (ref "R25")
      (value "4.7K")
      (footprint "eagle-import:R0402")
      (libsource (lib "eagle-import") (part "R-EU_R0402"))
    )
    (comp (ref "R26")
      (value "39K")
      (footprint "eagle-import:R0402")
      (libsource (lib "eagle-import") (part "R-EU_R0402"))
    )
    (comp (ref "R27")
      (value "10K")
      (footprint "eagle-import:R0402")
      (libsource (lib "eagle-import") (part "R-EU_R0402"))
    )
    (comp (ref "R28")
      (value "4.7K")
      (footprint "eagle-import:R0402")
      (libsource (lib "eagle-import") (part "R-EU_R0402"))
    )
    (comp (ref "R29")
      (value "0.1R")
      (footprint "eagle-import:R0805")
      (libsource (lib "eagle-import") (part "R-EU_R0805"))
    )
    (comp (ref "R30")
      (value "0.1R")
      (footprint "eagle-import:R0805")
      (libsource (lib "eagle-import") (part "R-EU_R0805"))
    )
    (comp (ref "R31")
      (value "10K")
      (footprint "eagle-import:R0402")
      (libsource (lib "eagle-import") (part "R-EU_R0402"))
    )
    (comp (ref "R32")
      (value "4.7K")
      (footprint "eagle-import:R0402")
      (libsource (lib "eagle-import") (part "R-EU_R0402"))
    )
    (comp (ref "R33")
      (value "4.7K")
      (footprint "eagle-import:R0402")
      (libsource (lib "eagle-import") (part "R-EU_R0402"))
    )
    (comp (ref "R34")
      (value "4.7K")
      (footprint "eagle-import:R0402")
      (libsource (lib "eagle-import") (part "R-EU_R0402"))
    )
    (comp (ref "R35")
      (value "10K")
      (footprint "eagle-import:R0402")
      (libsource (lib "eagle-import") (part "R-EU_R0402"))
    )
    (comp (ref "R36")
      (value "4.7K")
      (footprint "eagle-import:R0402")
      (libsource (lib "eagle-import") (part "R-EU_R0402"))
    )
    (comp (ref "R37")
      (value "10K")
      (footprint "eagle-import:R0402")
      (libsource (lib "eagle-import") (part "R-EU_R0402"))
    )
    (comp (ref "R38")
      (value "10K")
      (footprint "eagle-import:R0402")
      (libsource (lib "eagle-import") (part "R-EU_R0402"))
    )
    (comp (ref "R39")
      (value "10K")
      (footprint "eagle-import:R0402")
      (libsource (lib "eagle-import") (part "R-EU_R0402"))
    )
    (comp (ref "R40")
      (value "10K")
      (footprint "eagle-import:R0402")
      (libsource (lib "eagle-import") (part "R-EU_R0402"))
    )
    (comp (ref "R41")
      (value "10K")
      (footprint "eagle-import:R0402")
      (libsource (lib "eagle-import") (part "R-EU_R0402"))
    )
    (comp (ref "R42")
      (value "120K")
      (footprint "eagle-import:R0402")
      (libsource (lib "eagle-import") (part "R-EU_R0402"))
    )
    (comp (ref "R43")
      (value "10K")
      (footprint "eagle-import:R0402")
      (libsource (lib "eagle-import") (part "R-EU_R0402"))
    )
    (comp (ref "R44")
      (value "39K")
      (footprint "eagle-import:R0402")
      (libsource (lib "eagle-import") (part "R-EU_R0402"))
    )
    (comp (ref "R45")
      (value "4.7K")
      (footprint "eagle-import:R0402")
      (libsource (lib "eagle-import") (part "R-EU_R0402"))
    )
    (comp (ref "R46")
      (value "4.7K")
      (footprint "eagle-import:R0402")
      (libsource (lib "eagle-import") (part "R-EU_R0402"))
    )
    (comp (ref "R47")
      (value "4.7K")
      (footprint "eagle-import:R0402")
      (libsource (lib "eagle-import") (part "R-EU_R0402"))
    )
    (comp (ref "R48")
      (value "4.7K")
      (footprint "eagle-import:R0402")
      (libsource (lib "eagle-import") (part "R-EU_R0402"))
    )
    (comp (ref "R49")
      (value "10K")
      (footprint "eagle-import:R0402")
      (libsource (lib "eagle-import") (part "R-EU_R0402"))
    )
    (comp (ref "R50")
      (value "10K")
      (footprint "eagle-import:R0402")
      (libsource (lib "eagle-import") (part "R-EU_R0402"))
    )
    (comp (ref "R51")
      (value "4.7K")
      (footprint "eagle-import:R0402")
      (libsource (lib "eagle-import") (part "R-EU_R0402"))
    )
    (comp (ref "R52")
      (value "2.2R")
      (footprint "eagle-import:R0402")
      (libsource (lib "eagle-import") (part "R-EU_R0402"))
    )
    (comp (ref "R53")
      (value "2.2R")
      (footprint "eagle-import:R0402")
      (libsource (lib "eagle-import") (part "R-EU_R0402"))
    )
    (comp (ref "R54")
      (value "4.7K")
      (footprint "eagle-import:R0402")
      (libsource (lib "eagle-import") (part "R-EU_R0402"))
    )
    (comp (ref "R55")
      (value "4.7K")
      (footprint "eagle-import:R0402")
      (libsource (lib "eagle-import") (part "R-EU_R0402"))
    )
    (comp (ref "R56")
      (value "4.7K")
      (footprint "eagle-import:R0402")
      (libsource (lib "eagle-import") (part "R-EU_R0402"))
    )
    (comp (ref "R57")
      (value "4.7K")
      (footprint "eagle-import:R0402")
      (libsource (lib "eagle-import") (part "R-EU_R0402"))
    )
    (comp (ref "R58")
      (value "10K")
      (footprint "eagle-import:R0402")
      (libsource (lib "eagle-import") (part "R-EU_R0402"))
    )
    (comp (ref "R59")
      (value "2.2R")
      (footprint "eagle-import:R0402")
      (libsource (lib "eagle-import") (part "R-EU_R0402"))
    )
    (comp (ref "R60")
      (value "10K")
      (footprint "eagle-import:R0402")
      (libsource (lib "eagle-import") (part "R-EU_R0402"))
    )
    (comp (ref "R61")
      (value "4.7K")
      (footprint "eagle-import:R0402")
      (libsource (lib "eagle-import") (part "R-EU_R0402"))
    )
    (comp (ref "R62")
      (value "4.7K")
      (footprint "eagle-import:R0402")
      (libsource (lib "eagle-import") (part "R-EU_R0402"))
    )
    (comp (ref "R63")
      (value "4.7K")
      (footprint "eagle-import:R0402")
      (libsource (lib "eagle-import") (part "R-EU_R0402"))
    )
    (comp (ref "R64")
      (value "4.7K")
      (footprint "eagle-import:R0402")
      (libsource (lib "eagle-import") (part "R-EU_R0402"))
    )
    (comp (ref "R65")
      (value "4.7K")
      (footprint "eagle-import:R0402")
      (libsource (lib "eagle-import") (part "R-EU_R0402"))
    )
    (comp (ref "R66")
      (value "4.7K")
      (footprint "eagle-import:R0402")
      (libsource (lib "eagle-import") (part "R-EU_R0402"))
    )
    (comp (ref "R70")
      (value "2.2R")
      (footprint "eagle-import:R0402")
      (libsource (lib "eagle-import") (part "R-EU_R0402"))
    )
    (comp (ref "R71")
      (value "2.2R")
      (footprint "eagle-import:R0402")
      (libsource (lib "eagle-import") (part "R-EU_R0402"))
    )
    (comp (ref "U$3")
      (value "CC-BY-SA")
      (footprint "eagle-import:CC-BY-SA")
      (libsource (lib "eagle-import") (part "CC-BY-SA"))
    )
    (comp (ref "U1")
      (value "SN74AHC595PW")
      (footprint "eagle-import:SOP65P640X120-16N")
      (libsource (lib "eagle-import") (part "SN74AHC595PW"))
    )
    (comp (ref "U2")
      (value "SN74AHC595PW")
      (footprint "eagle-import:SOP65P640X120-16N")
      (libsource (lib "eagle-import") (part "SN74AHC595PW"))
    )
    (comp (ref "U3")
      (value "SN74AHC595PW")
      (footprint "eagle-import:SOP65P640X120-16N")
      (libsource (lib "eagle-import") (part "SN74AHC595PW"))
    )
    (comp (ref "U4")
      (value "SN74AHC595PW")
      (footprint "eagle-import:SOP65P640X120-16N")
      (libsource (lib "eagle-import") (part "SN74AHC595PW"))
    )
    (comp (ref "U5")
      (value "SN74AHC595PW")
      (footprint "eagle-import:SOP65P640X120-16N")
      (libsource (lib "eagle-import") (part "SN74AHC595PW"))
    )
    (comp (ref "U6")
      (value "RT8268")
      (footprint "eagle-import:MSOP10")
      (libsource (lib "eagle-import") (part "RT8268"))
    )
    (comp (ref "U10")
      (value "RT8268")
      (footprint "eagle-import:MSOP10")
      (libsource (lib "eagle-import") (part "RT8268"))
    )
    (comp (ref "U11")
      (value "PCA9685PW")
      (footprint "eagle-import:SOP65P640X110-28N")
      (libsource (lib "eagle-import") (part "PCA9685PW"))
    )
    (comp (ref "U18")
      (value "CAT24C256")
      (footprint "eagle-import:SOIC127P600X175-8N")
      (libsource (lib "eagle-import") (part "CAT24C256"))
    )
    (comp (ref "U19")
      (value "CD4050BD")
      (footprint "eagle-import:SOIC127P600X175-16N")
      (libsource (lib "eagle-import") (part "CD4050BD"))
    )
    (comp (ref "X1")
      (value "22-05-7038-03")
      (footprint "eagle-import:7395-03")
      (libsource (lib "eagle-import") (part "22-?-0305-7038"))
    )
    (comp (ref "X2")
      (value "MSTBA4")
      (footprint "eagle-import:MSTBA4")
      (fields (field (name "MF") "FARNELL") (field (name "MPN") "1757268"))
      (libsource (lib "eagle-import") (part "MSTBA4"))
    )
    (comp (ref "X3")
      (value "MSTBA2")
      (footprint "eagle-import:MSTBA2")
      (fields (field (name "MF") "FARNELL") (field (name "MPN") "1757242"))
      (libsource (lib "eagle-import") (part "MSTBA2"))
    )
    (comp (ref "X4")
      (value "22-05-7028-02")
      (footprint "eagle-import:7395-02")
      (libsource (lib "eagle-import") (part "22-?-0205-7028"))
    )
    (comp (ref "X5")
      (value "22-05-7028-02")
      (footprint "eagle-import:7395-02")
      (libsource (lib "eagle-import") (part "22-?-0205-7028"))
    )
    (comp (ref "X6")
      (value "22-05-7028-02")
      (footprint "eagle-import:7395-02")
      (libsource (lib "eagle-import") (part "22-?-0205-7028"))
    )
    (comp (ref "X7")
      (value "22-05-7028-02")
      (footprint "eagle-import:7395-02")
      (libsource (lib "eagle-import") (part "22-?-0205-7028"))
    )
    (comp (ref "X8")
      (value "22-05-7028-02")
      (footprint "eagle-import:7395-02")
      (libsource (lib "eagle-import") (part "22-?-0205-7028"))
    )
    (comp (ref "X9")
      (value "22-05-7028-02")
      (footprint "eagle-import:7395-02")
      (libsource (lib "eagle-import") (part "22-?-0205-7028"))
    )
    (comp (ref "X10")
      (value "22-05-7038-03")
      (footprint "eagle-import:7395-03")
      (libsource (lib "eagle-import") (part "22-?-0305-7038"))
    )
    (comp (ref "X11")
      (value "22-05-7028-02")
      (footprint "eagle-import:7395-02")
      (libsource (lib "eagle-import") (part "22-?-0205-7028"))
    )
    (comp (ref "X12")
      (value "22-05-7048-04")
      (footprint "eagle-import:7395-04")
      (libsource (lib "eagle-import") (part "22-?-0405-7048"))
    )
    (comp (ref "X13")
      (value "22-05-7038-03")
      (footprint "eagle-import:7395-03")
      (libsource (lib "eagle-import") (part "22-?-0305-7038"))
    )
    (comp (ref "X14")
      (value "22-05-7048-04")
      (footprint "eagle-import:7395-04")
      (libsource (lib "eagle-import") (part "22-?-0405-7048"))
    )
    (comp (ref "X15")
      (value "22-05-7048-04")
      (footprint "eagle-import:7395-04")
      (libsource (lib "eagle-import") (part "22-?-0405-7048"))
    )
    (comp (ref "X16")
      (value "22-05-7048-04")
      (footprint "eagle-import:7395-04")
      (libsource (lib "eagle-import") (part "22-?-0405-7048"))
    )
    (comp (ref "X17")
      (value "22-05-7048-04")
      (footprint "eagle-import:7395-04")
      (libsource (lib "eagle-import") (part "22-?-0405-7048"))
    )
    (comp (ref "X18")
      (value "22-05-7048-04")
      (footprint "eagle-import:7395-04")
      (libsource (lib "eagle-import") (part "22-?-0405-7048"))
    )
    (comp (ref "X19")
      (value "22-05-7038-03")
      (footprint "eagle-import:7395-03")
      (libsource (lib "eagle-import") (part "22-?-0305-7038"))
    )
    (comp (ref "X20")
      (value "MSTBA4")
      (footprint "eagle-import:MSTBA4")
      (fields (field (name "MF") "FARNELL") (field (name "MPN") "1757268"))
      (libsource (lib "eagle-import") (part "MSTBA4"))
    )
    (comp (ref "X21")
      (value "MSTBA2")
      (footprint "eagle-import:MSTBA2")
      (fields (field (name "MF") "FARNELL") (field (name "MPN") "1757242"))
      (libsource (lib "eagle-import") (part "MSTBA2"))
    )
    (comp (ref "X22")
      (value "22-05-7038-03")
      (footprint "eagle-import:7395-03")
      (libsource (lib "eagle-import") (part "22-?-0305-7038"))
    )
    (comp (ref "X23")
      (value "22-05-7038-03")
      (footprint "eagle-import:7395-03")
      (libsource (lib "eagle-import") (part "22-?-0305-7038"))
    )
  )
  (nets
    (net (code "1") (name "+3V3") (class "Default")
      (node (ref "3.3V") (pin "TP") (pinfunction "TP_TP") (pintype "input"))
      (node (ref "C13") (pin "1") (pinfunction "1_1") (pintype "passive"))
      (node (ref "C14") (pin "1") (pinfunction "1_1") (pintype "passive"))
      (node (ref "C15") (pin "1") (pinfunction "1_1") (pintype "passive"))
      (node (ref "C2") (pin "1") (pinfunction "1_1") (pintype "passive"))
      (node (ref "C23") (pin "1") (pinfunction "1_1") (pintype "passive"))
      (node (ref "C30") (pin "1") (pinfunction "1_1") (pintype "passive"))
      (node (ref "C41") (pin "1") (pinfunction "1_1") (pintype "passive"))
      (node (ref "C42") (pin "1") (pinfunction "1_1") (pintype "passive"))
      (node (ref "C44") (pin "1") (pinfunction "1_1") (pintype "passive"))
      (node (ref "C5") (pin "1") (pinfunction "1_1") (pintype "passive"))
      (node (ref "C61") (pin "1") (pinfunction "1_1") (pintype "passive"))
      (node (ref "C63") (pin "1") (pinfunction "1_1") (pintype "passive"))
      (node (ref "C84") (pin "1") (pinfunction "1_1") (pintype "passive"))
      (node (ref "C85") (pin "1") (pinfunction "1_1") (pintype "passive"))
      (node (ref "C86") (pin "1") (pinfunction "1_1") (pintype "passive"))
      (node (ref "C87") (pin "1") (pinfunction "1_1") (pintype "passive"))
      (node (ref "C88") (pin "1") (pinfunction "1_1") (pintype "passive"))
      (node (ref "IC1") (pin "8") (pinfunction "VCC_IO_8") (pintype "bidirectional"))
      (node (ref "IC10") (pin "5") (pinfunction "VCC_5") (pintype "power_in"))
      (node (ref "IC11") (pin "5") (pinfunction "VCC_5") (pintype "power_in"))
      (node (ref "IC12") (pin "8") (pinfunction "VCC_IO_8") (pintype "bidirectional"))
      (node (ref "IC13") (pin "5") (pinfunction "VCC_5") (pintype "power_in"))
      (node (ref "IC14") (pin "5") (pinfunction "VCC_5") (pintype "power_in"))
      (node (ref "IC15") (pin "8") (pinfunction "VCC_IO_8") (pintype "bidirectional"))
      (node (ref "IC16") (pin "5") (pinfunction "VCC_5") (pintype "power_in"))
      (node (ref "IC17") (pin "5") (pinfunction "VCC_5") (pintype "power_in"))
      (node (ref "IC2") (pin "8") (pinfunction "VCC_IO_8") (pintype "bidirectional"))
      (node (ref "IC3") (pin "5") (pinfunction "VCC_5") (pintype "power_in"))
      (node (ref "IC4") (pin "5") (pinfunction "VCC_5") (pintype "power_in"))
      (node (ref "IC5") (pin "8") (pinfunction "VCC_IO_8") (pintype "bidirectional"))
      (node (ref "IC8") (pin "5") (pinfunction "VCC_5") (pintype "power_in"))
      (node (ref "IC9") (pin "5") (pinfunction "VCC_5") (pintype "power_in"))
      (node (ref "P9") (pin "3") (pinfunction "3_3") (pintype "passive"))
      (node (ref "P9") (pin "4") (pinfunction "4_4") (pintype "passive"))
      (node (ref "R23") (pin "2") (pinfunction "2_2") (pintype "passive"))
      (node (ref "R24") (pin "2") (pinfunction "2_2") (pintype "passive"))
      (node (ref "R28") (pin "2") (pinfunction "2_2") (pintype "passive"))
      (node (ref "R36") (pin "2") (pinfunction "2_2") (pintype "passive"))
      (node (ref "R51") (pin "2") (pinfunction "2_2") (pintype "passive"))
      (node (ref "R54") (pin "2") (pinfunction "2_2") (pintype "passive"))
      (node (ref "U1") (pin "10") (pinfunction "~{SRCLR}_10") (pintype "input"))
      (node (ref "U1") (pin "16") (pinfunction "VCC_16") (pintype "power_in"))
      (node (ref "U18") (pin "3") (pinfunction "A2_3") (pintype "input"))
      (node (ref "U18") (pin "8") (pinfunction "VCC_8") (pintype "power_in"))
      (node (ref "U19") (pin "1") (pinfunction "VCC_1") (pintype "power_in"))
      (node (ref "U2") (pin "10") (pinfunction "~{SRCLR}_10") (pintype "input"))
      (node (ref "U2") (pin "16") (pinfunction "VCC_16") (pintype "power_in"))
      (node (ref "U3") (pin "10") (pinfunction "~{SRCLR}_10") (pintype "input"))
      (node (ref "U3") (pin "16") (pinfunction "VCC_16") (pintype "power_in"))
      (node (ref "U4") (pin "10") (pinfunction "~{SRCLR}_10") (pintype "input"))
      (node (ref "U4") (pin "16") (pinfunction "VCC_16") (pintype "power_in"))
      (node (ref "U5") (pin "10") (pinfunction "~{SRCLR}_10") (pintype "input"))
      (node (ref "U5") (pin "16") (pinfunction "VCC_16") (pintype "power_in"))
      (node (ref "X23") (pin "1") (pinfunction "S_1") (pintype "passive"))
    )
    (net (code "2") (name "+5V") (class "Default")
      (node (ref "5V") (pin "TP") (pinfunction "TP_TP") (pintype "input"))
      (node (ref "C17") (pin "1") (pinfunction "1_1") (pintype "passive"))
      (node (ref "C48") (pin "1") (pinfunction "1_1") (pintype "passive"))
      (node (ref "C80") (pin "1") (pinfunction "1_1") (pintype "passive"))
      (node (ref "C82") (pin "1") (pinfunction "1_1") (pintype "passive"))
      (node (ref "C83") (pin "1") (pinfunction "1_1") (pintype "passive"))
      (node (ref "IC6") (pin "5") (pinfunction "VCC_5") (pintype "power_in"))
      (node (ref "IC7") (pin "5") (pinfunction "VCC_5") (pintype "power_in"))
      (node (ref "L1") (pin "P$1") (pinfunction "P$1_P$1") (pintype "passive"))
      (node (ref "P9") (pin "5") (pinfunction "5_5") (pintype "passive"))
      (node (ref "P9") (pin "6") (pinfunction "6_6") (pintype "passive"))
      (node (ref "R12") (pin "1") (pinfunction "1_1") (pintype "passive"))
      (node (ref "R61") (pin "2") (pinfunction "2_2") (pintype "passive"))
      (node (ref "R62") (pin "2") (pinfunction "2_2") (pintype "passive"))
      (node (ref "R63") (pin "2") (pinfunction "2_2") (pintype "passive"))
      (node (ref "R64") (pin "2") (pinfunction "2_2") (pintype "passive"))
      (node (ref "R65") (pin "2") (pinfunction "2_2") (pintype "passive"))
      (node (ref "R66") (pin "2") (pinfunction "2_2") (pintype "passive"))
      (node (ref "U11") (pin "1") (pinfunction "A0_1") (pintype "input"))
      (node (ref "U11") (pin "2") (pinfunction "A1_2") (pintype "input"))
      (node (ref "U11") (pin "24") (pinfunction "A5_24") (pintype "input"))
      (node (ref "U11") (pin "28") (pinfunction "VDD_28") (pintype "power_in"))
      (node (ref "U11") (pin "3") (pinfunction "A2_3") (pintype "input"))
      (node (ref "U11") (pin "4") (pinfunction "A3_4") (pintype "input"))
      (node (ref "U11") (pin "5") (pinfunction "A4_5") (pintype "input"))
      (node (ref "X1") (pin "2") (pinfunction "S_2") (pintype "passive"))
      (node (ref "X10") (pin "2") (pinfunction "S_2") (pintype "passive"))
      (node (ref "X12") (pin "2") (pinfunction "S_2") (pintype "passive"))
      (node (ref "X13") (pin "2") (pinfunction "S_2") (pintype "passive"))
      (node (ref "X19") (pin "2") (pinfunction "S_2") (pintype "passive"))
      (node (ref "X22") (pin "2") (pinfunction "S_2") (pintype "passive"))
    )
    (net (code "3") (name "/DALLAS_W1") (class "Default")
      (node (ref "P9") (pin "22") (pinfunction "22_22") (pintype "passive"))
      (node (ref "X23") (pin "2") (pinfunction "S_2") (pintype "passive"))
    )
    (net (code "4") (name "/DIR_E") (class "Default")
      (node (ref "IC12") (pin "7") (pinfunction "REFR_DIR_7") (pintype "bidirectional"))
      (node (ref "P8") (pin "15") (pinfunction "15_15") (pintype "passive"))
    )
    (net (code "5") (name "/DIR_H") (class "Default")
      (node (ref "IC15") (pin "7") (pinfunction "REFR_DIR_7") (pintype "bidirectional"))
      (node (ref "P8") (pin "16") (pinfunction "16_16") (pintype "passive"))
    )
    (net (code "6") (name "/DIR_X") (class "Default")
      (node (ref "IC1") (pin "7") (pinfunction "REFR_DIR_7") (pintype "bidirectional"))
      (node (ref "P8") (pin "26") (pinfunction "26_26") (pintype "passive"))
    )
    (net (code "7") (name "/DIR_Y") (class "Default")
      (node (ref "IC2") (pin "7") (pinfunction "REFR_DIR_7") (pintype "bidirectional"))
      (node (ref "P8") (pin "19") (pinfunction "19_19") (pintype "passive"))
    )
    (net (code "8") (name "/DIR_Z") (class "Default")
      (node (ref "IC5") (pin "7") (pinfunction "REFR_DIR_7") (pintype "bidirectional"))
      (node (ref "P8") (pin "14") (pinfunction "14_14") (pintype "passive"))
    )
    (net (code "9") (name "/ENABLE") (class "Default")
      (node (ref "P9") (pin "41") (pinfunction "41_41") (pintype "passive"))
      (node (ref "R23") (pin "1") (pinfunction "1_1") (pintype "passive"))
      (node (ref "U11") (pin "23") (pinfunction "~{OE}_23") (pintype "input"))
    )
    (net (code "10") (name "/ENABLE_E") (class "Default")
      (node (ref "IC12") (pin "22") (pinfunction "DRV_ENN_CFG6_22") (pintype "bidirectional"))
      (node (ref "U4") (pin "15") (pinfunction "QA_15") (pintype "output"))
    )
    (net (code "11") (name "/ENABLE_XYZ") (class "Default")
      (node (ref "IC1") (pin "22") (pinfunction "DRV_ENN_CFG6_22") (pintype "bidirectional"))
      (node (ref "IC2") (pin "22") (pinfunction "DRV_ENN_CFG6_22") (pintype "bidirectional"))
      (node (ref "IC5") (pin "22") (pinfunction "DRV_ENN_CFG6_22") (pintype "bidirectional"))
      (node (ref "U1") (pin "15") (pinfunction "QA_15") (pintype "output"))
    )
    (net (code "12") (name "/END_STOP_X_1") (class "Default")
      (node (ref "P9") (pin "25") (pinfunction "25_25") (pintype "passive"))
      (node (ref "U19") (pin "2") (pinfunction "G=A_2") (pintype "output"))
    )
    (net (code "13") (name "/END_STOP_X_1_IN") (class "Default")
      (node (ref "R61") (pin "1") (pinfunction "1_1") (pintype "passive"))
      (node (ref "U19") (pin "3") (pinfunction "A_3") (pintype "input"))
      (node (ref "X22") (pin "1") (pinfunction "S_1") (pintype "passive"))
    )
    (net (code "14") (name "/END_STOP_X_2") (class "Default")
      (node (ref "P9") (pin "11") (pinfunction "11_11") (pintype "passive"))
      (node (ref "U19") (pin "10") (pinfunction "J=D_10") (pintype "output"))
    )
    (net (code "15") (name "/END_STOP_X_2_IN") (class "Default")
      (node (ref "IC6") (pin "4") (pinfunction "O_4") (pintype "output"))
      (node (ref "R64") (pin "1") (pinfunction "1_1") (pintype "passive"))
      (node (ref "U19") (pin "9") (pinfunction "D_9") (pintype "input"))
      (node (ref "X10") (pin "1") (pinfunction "S_1") (pintype "passive"))
    )
    (net (code "16") (name "/END_STOP_Y_1") (class "Default")
      (node (ref "P9") (pin "23") (pinfunction "23_23") (pintype "passive"))
      (node (ref "U19") (pin "4") (pinfunction "H=B_4") (pintype "output"))
    )
    (net (code "17") (name "/END_STOP_Y_1_IN") (class "Default")
      (node (ref "R62") (pin "1") (pinfunction "1_1") (pintype "passive"))
      (node (ref "U19") (pin "5") (pinfunction "B_5") (pintype "input"))
      (node (ref "X1") (pin "1") (pinfunction "S_1") (pintype "passive"))
    )
    (net (code "18") (name "/END_STOP_Y_2") (class "Default")
      (node (ref "P9") (pin "28") (pinfunction "28_28") (pintype "passive"))
      (node (ref "U19") (pin "12") (pinfunction "K=E_12") (pintype "output"))
    )
    (net (code "19") (name "/END_STOP_Y_2_IN") (class "Default")
      (node (ref "IC7") (pin "4") (pinfunction "O_4") (pintype "output"))
      (node (ref "R65") (pin "1") (pinfunction "1_1") (pintype "passive"))
      (node (ref "U19") (pin "11") (pinfunction "E_11") (pintype "input"))
      (node (ref "X19") (pin "1") (pinfunction "S_1") (pintype "passive"))
    )
    (net (code "20") (name "/END_STOP_Z_1") (class "Default")
      (node (ref "P9") (pin "13") (pinfunction "13_13") (pintype "passive"))
      (node (ref "U19") (pin "6") (pinfunction "I=C_6") (pintype "output"))
    )
    (net (code "21") (name "/END_STOP_Z_1_IN") (class "Default")
      (node (ref "R63") (pin "1") (pinfunction "1_1") (pintype "passive"))
      (node (ref "U19") (pin "7") (pinfunction "C_7") (pintype "input"))
      (node (ref "X13") (pin "1") (pinfunction "S_1") (pintype "passive"))
    )
    (net (code "22") (name "/END_STOP_Z_2") (class "Default")
      (node (ref "P9") (pin "18") (pinfunction "18_18") (pintype "passive"))
      (node (ref "U19") (pin "15") (pinfunction "L=F_15") (pintype "output"))
    )
    (net (code "23") (name "/END_STOP_Z_2_IN") (class "Default")
      (node (ref "R66") (pin "1") (pinfunction "1_1") (pintype "passive"))
      (node (ref "U19") (pin "14") (pinfunction "F_14") (pintype "input"))
      (node (ref "X12") (pin "1") (pinfunction "S_1") (pintype "passive"))
    )
    (net (code "24") (name "/FAN0") (class "Default")
      (node (ref "Q6") (pin "1") (pinfunction "B_1") (pintype "passive"))
      (node (ref "R34") (pin "2") (pinfunction "2_2") (pintype "passive"))
      (node (ref "U11") (pin "13") (pinfunction "LED7_13") (pintype "output"))
    )
    (net (code "25") (name "/FAN1") (class "Default")
      (node (ref "Q7") (pin "1") (pinfunction "B_1") (pintype "passive"))
      (node (ref "R33") (pin "2") (pinfunction "2_2") (pintype "passive"))
      (node (ref "U11") (pin "15") (pinfunction "LED8_15") (pintype "output"))
    )
    (net (code "26") (name "/FAN2") (class "Default")
      (node (ref "Q4") (pin "1") (pinfunction "B_1") (pintype "passive"))
      (node (ref "R32") (pin "2") (pinfunction "2_2") (pintype "passive"))
      (node (ref "U11") (pin "16") (pinfunction "LED9_16") (pintype "output"))
    )
    (net (code "27") (name "/FAN3") (class "Default")
      (node (ref "Q5") (pin "1") (pinfunction "B_1") (pintype "passive"))
      (node (ref "R5") (pin "2") (pinfunction "2_2") (pintype "passive"))
      (node (ref "U11") (pin "17") (pinfunction "LED10_17") (pintype "output"))
    )
    (net (code "28") (name "/FAULT_E") (class "Default")
      (node (ref "IC12") (pin "20") (pinfunction "SWN_DIAG0_20") (pintype "bidirectional"))
      (node (ref "P8") (pin "18") (pinfunction "18_18") (pintype "passive"))
      (node (ref "R36") (pin "1") (pinfunction "1_1") (pintype "passive"))
    )
    (net (code "29") (name "/FAULT_H") (class "Default")
      (node (ref "IC15") (pin "20") (pinfunction "SWN_DIAG0_20") (pintype "bidirectional"))
      (node (ref "P8") (pin "8") (pinfunction "8_8") (pintype "passive"))
      (node (ref "R51") (pin "1") (pinfunction "1_1") (pintype "passive"))
    )
    (net (code "30") (name "/FAULT_X") (class "Default")
      (node (ref "IC1") (pin "20") (pinfunction "SWN_DIAG0_20") (pintype "bidirectional"))
      (node (ref "P8") (pin "10") (pinfunction "10_10") (pintype "passive"))
      (node (ref "R54") (pin "1") (pinfunction "1_1") (pintype "passive"))
    )
    (net (code "31") (name "/FAULT_Y") (class "Default")
      (node (ref "IC2") (pin "20") (pinfunction "SWN_DIAG0_20") (pintype "bidirectional"))
      (node (ref "P8") (pin "9") (pinfunction "9_9") (pintype "passive"))
      (node (ref "R24") (pin "1") (pinfunction "1_1") (pintype "passive"))
    )
    (net (code "32") (name "/FAULT_Z") (class "Default")
      (node (ref "IC5") (pin "20") (pinfunction "SWN_DIAG0_20") (pintype "bidirectional"))
      (node (ref "P9") (pin "24") (pinfunction "24_24") (pintype "passive"))
      (node (ref "R28") (pin "1") (pinfunction "1_1") (pintype "passive"))
    )
    (net (code "33") (name "/HEATER_E") (class "Default")
      (node (ref "Q3") (pin "4") (pinfunction "G_4") (pintype "passive"))
      (node (ref "R47") (pin "2") (pinfunction "2_2") (pintype "passive"))
      (node (ref "U11") (pin "11") (pinfunction "LED5_11") (pintype "output"))
    )
    (net (code "34") (name "/HEATER_H") (class "Default")
      (node (ref "Q2") (pin "4") (pinfunction "G_4") (pintype "passive"))
      (node (ref "R48") (pin "2") (pinfunction "2_2") (pintype "passive"))
      (node (ref "U11") (pin "9") (pinfunction "LED3_9") (pintype "output"))
    )
    (net (code "35") (name "/HEATER_HBP") (class "Default")
      (node (ref "Q1") (pin "4") (pinfunction "G_4") (pintype "passive"))
      (node (ref "R46") (pin "2") (pinfunction "2_2") (pintype "passive"))
      (node (ref "U11") (pin "10") (pinfunction "LED4_10") (pintype "output"))
    )
    (net (code "36") (name "/I2C2_SCL") (class "Default")
      (node (ref "P9") (pin "19") (pinfunction "19_19") (pintype "passive"))
      (node (ref "U11") (pin "26") (pinfunction "SCL_26") (pintype "input"))
      (node (ref "U18") (pin "6") (pinfunction "SCL_6") (pintype "input"))
    )
    (net (code "37") (name "/I2C2_SDA") (class "Default")
      (node (ref "P9") (pin "20") (pinfunction "20_20") (pintype "passive"))
      (node (ref "U11") (pin "27") (pinfunction "SDA_27") (pintype "bidirectional"))
      (node (ref "U18") (pin "5") (pinfunction "SDA_5") (pintype "bidirectional"))
    )
    (net (code "38") (name "/IREF_E_RAW") (class "Default")
      (node (ref "R60") (pin "2") (pinfunction "2_2") (pintype "passive"))
      (node (ref "U11") (pin "21") (pinfunction "LED14_21") (pintype "output"))
    )
    (net (code "39") (name "/IREF_H_RAW") (class "Default")
      (node (ref "R31") (pin "2") (pinfunction "2_2") (pintype "passive"))
      (node (ref "U11") (pin "22") (pinfunction "LED15_22") (pintype "output"))
    )
    (net (code "40") (name "/IREF_X_RAW") (class "Default")
      (node (ref "R41") (pin "2") (pinfunction "2_2") (pintype "passive"))
      (node (ref "U11") (pin "18") (pinfunction "LED11_18") (pintype "output"))
    )
    (net (code "41") (name "/IREF_Y_RAW") (class "Default")
      (node (ref "R37") (pin "2") (pinfunction "2_2") (pintype "passive"))
      (node (ref "U11") (pin "19") (pinfunction "LED12_19") (pintype "output"))
    )
    (net (code "42") (name "/IREF_Z_RAW") (class "Default")
      (node (ref "R58") (pin "2") (pinfunction "2_2") (pintype "passive"))
      (node (ref "U11") (pin "20") (pinfunction "LED13_20") (pintype "output"))
    )
    (net (code "43") (name "/SERVO_0") (class "Default")
      (node (ref "IC6") (pin "2") (pinfunction "I_2") (pintype "input"))
      (node (ref "P9") (pin "14") (pinfunction "14_14") (pintype "passive"))
    )
    (net (code "44") (name "/SERVO_0_EN") (class "Default")
      (node (ref "IC6") (pin "1") (pinfunction "OE_1") (pintype "input"))
      (node (ref "U2") (pin "15") (pinfunction "QA_15") (pintype "output"))
    )
    (net (code "45") (name "/SERVO_1") (class "Default")
      (node (ref "IC7") (pin "2") (pinfunction "I_2") (pintype "input"))
      (node (ref "P9") (pin "16") (pinfunction "16_16") (pintype "passive"))
    )
    (net (code "46") (name "/SERVO_1_EN") (class "Default")
      (node (ref "IC7") (pin "1") (pinfunction "OE_1") (pintype "input"))
      (node (ref "U3") (pin "15") (pinfunction "QA_15") (pintype "output"))
    )
    (net (code "47") (name "/SER_2") (class "Default")
      (node (ref "U1") (pin "9") (pinfunction "QH_2_9") (pintype "output"))
      (node (ref "U2") (pin "14") (pinfunction "SER_14") (pintype "input"))
    )
    (net (code "48") (name "/SER_3") (class "Default")
      (node (ref "U2") (pin "9") (pinfunction "QH_2_9") (pintype "output"))
      (node (ref "U3") (pin "14") (pinfunction "SER_14") (pintype "input"))
    )
    (net (code "49") (name "/SER_4") (class "Default")
      (node (ref "U3") (pin "9") (pinfunction "QH_2_9") (pintype "output"))
      (node (ref "U4") (pin "14") (pinfunction "SER_14") (pintype "input"))
    )
    (net (code "50") (name "/SER_5") (class "Default")
      (node (ref "U4") (pin "9") (pinfunction "QH_2_9") (pintype "output"))
      (node (ref "U5") (pin "14") (pinfunction "SER_14") (pintype "input"))
    )
    (net (code "51") (name "/SPI1_CS1") (class "Default")
      (node (ref "P9") (pin "42") (pinfunction "42_42") (pintype "passive"))
      (node (ref "U1") (pin "12") (pinfunction "RCLK_12") (pintype "input"))
      (node (ref "U2") (pin "12") (pinfunction "RCLK_12") (pintype "input"))
      (node (ref "U3") (pin "12") (pinfunction "RCLK_12") (pintype "input"))
      (node (ref "U4") (pin "12") (pinfunction "RCLK_12") (pintype "input"))
      (node (ref "U5") (pin "12") (pinfunction "RCLK_12") (pintype "input"))
    )
    (net (code "52") (name "/SPI1_MOSI") (class "Default")
      (node (ref "P9") (pin "30") (pinfunction "30_30") (pintype "passive"))
      (node (ref "U1") (pin "14") (pinfunction "SER_14") (pintype "input"))
    )
    (net (code "53") (name "/SPI1_SCLK") (class "Default")
      (node (ref "P9") (pin "31") (pinfunction "31_31") (pintype "passive"))
      (node (ref "U1") (pin "11") (pinfunction "SRCLK_11") (pintype "input"))
      (node (ref "U2") (pin "11") (pinfunction "SRCLK_11") (pintype "input"))
      (node (ref "U3") (pin "11") (pinfunction "SRCLK_11") (pintype "input"))
      (node (ref "U4") (pin "11") (pinfunction "SRCLK_11") (pintype "input"))
      (node (ref "U5") (pin "11") (pinfunction "SRCLK_11") (pintype "input"))
    )
    (net (code "54") (name "/STEP_E") (class "Default")
      (node (ref "IC12") (pin "6") (pinfunction "REFL_STEP_6") (pintype "bidirectional"))
      (node (ref "P9") (pin "12") (pinfunction "12_12") (pintype "passive"))
    )
    (net (code "55") (name "/STEP_H") (class "Default")
      (node (ref "IC15") (pin "6") (pinfunction "REFL_STEP_6") (pintype "bidirectional"))
      (node (ref "P8") (pin "11") (pinfunction "11_11") (pintype "passive"))
    )
    (net (code "56") (name "/STEP_X") (class "Default")
      (node (ref "IC1") (pin "6") (pinfunction "REFL_STEP_6") (pintype "bidirectional"))
      (node (ref "P8") (pin "17") (pinfunction "17_17") (pintype "passive"))
    )
    (net (code "57") (name "/STEP_Y") (class "Default")
      (node (ref "IC2") (pin "6") (pinfunction "REFL_STEP_6") (pintype "bidirectional"))
      (node (ref "P8") (pin "12") (pinfunction "12_12") (pintype "passive"))
    )
    (net (code "58") (name "/STEP_Z") (class "Default")
      (node (ref "IC5") (pin "6") (pinfunction "REFL_STEP_6") (pintype "bidirectional"))
      (node (ref "P8") (pin "13") (pinfunction "13_13") (pintype "passive"))
    )
    (net (code "59") (name "/TERM_EXT1") (class "Default")
      (node (ref "C26") (pin "1") (pinfunction "1_1") (pintype "passive"))
      (node (ref "P9") (pin "33") (pinfunction "33_33") (pintype "passive"))
      (node (ref "R38") (pin "2") (pinfunction "2_2") (pintype "passive"))
    )
    (net (code "60") (name "/TERM_EXT2") (class "Default")
      (node (ref "C46") (pin "1") (pinfunction "1_1") (pintype "passive"))
      (node (ref "P9") (pin "36") (pinfunction "36_36") (pintype "passive"))
      (node (ref "R40") (pin "2") (pinfunction "2_2") (pintype "passive"))
    )
    (net (code "61") (name "/TERM_HBP") (class "Default")
      (node (ref "C45") (pin "1") (pinfunction "1_1") (pintype "passive"))
      (node (ref "P9") (pin "35") (pinfunction "35_35") (pintype "passive"))
      (node (ref "R39") (pin "2") (pinfunction "2_2") (pintype "passive"))
    )
    (net (code "62") (name "/VDD_12V") (class "Default")
      (node (ref "12V") (pin "TP") (pinfunction "TP_TP") (pintype "input"))
      (node (ref "C53") (pin "1") (pinfunction "1_1") (pintype "passive"))
      (node (ref "C81") (pin "1") (pinfunction "1_1") (pintype "passive"))
      (node (ref "L2") (pin "P$1") (pinfunction "P$1_P$1") (pintype "passive"))
      (node (ref "R11") (pin "2") (pinfunction "2_2") (pintype "passive"))
      (node (ref "R19") (pin "2") (pinfunction "2_2") (pintype "passive"))
      (node (ref "R20") (pin "2") (pinfunction "2_2") (pintype "passive"))
      (node (ref "R21") (pin "2") (pinfunction "2_2") (pintype "passive"))
      (node (ref "R25") (pin "2") (pinfunction "2_2") (pintype "passive"))
      (node (ref "R42") (pin "1") (pinfunction "1_1") (pintype "passive"))
      (node (ref "X12") (pin "4") (pinfunction "S_4") (pintype "passive"))
      (node (ref "X4") (pin "1") (pinfunction "S_1") (pintype "passive"))
      (node (ref "X5") (pin "1") (pinfunction "S_1") (pintype "passive"))
      (node (ref "X6") (pin "1") (pinfunction "S_1") (pintype "passive"))
      (node (ref "X9") (pin "1") (pinfunction "S_1") (pintype "passive"))
    )
    (net (code "63") (name "/VDD_ADC") (class "Default")
      (node (ref "P9") (pin "32") (pinfunction "32_32") (pintype "passive"))
      (node (ref "R13") (pin "2") (pinfunction "2_2") (pintype "passive"))
      (node (ref "R17") (pin "2") (pinfunction "2_2") (pintype "passive"))
      (node (ref "R18") (pin "2") (pinfunction "2_2") (pintype "passive"))
    )
    (net (code "64") (name "/VDD_IN") (class "Default")
      (node (ref "12..24V") (pin "TP") (pinfunction "TP_TP") (pintype "input"))
      (node (ref "C10") (pin "1") (pinfunction "1_1") (pintype "passive"))
      (node (ref "C11") (pin "1") (pinfunction "1_1") (pintype "passive"))
      (node (ref "C16") (pin "1") (pinfunction "1_1") (pintype "passive"))
      (node (ref "C19") (pin "1") (pinfunction "1_1") (pintype "passive"))
      (node (ref "C20") (pin "2") (pinfunction "2_2") (pintype "passive"))
      (node (ref "C22") (pin "2") (pinfunction "2_2") (pintype "passive"))
      (node (ref "C24") (pin "1") (pinfunction "1_1") (pintype "passive"))
      (node (ref "C27") (pin "1") (pinfunction "1_1") (pintype "passive"))
      (node (ref "C28") (pin "2") (pinfunction "2_2") (pintype "passive"))
      (node (ref "C29") (pin "1") (pinfunction "1_1") (pintype "passive"))
      (node (ref "C31") (pin "1") (pinfunction "1_1") (pintype "passive"))
      (node (ref "C32") (pin "2") (pinfunction "2_2") (pintype "passive"))
      (node (ref "C34") (pin "1") (pinfunction "1_1") (pintype "passive"))
      (node (ref "C35") (pin "2") (pinfunction "2_2") (pintype "passive"))
      (node (ref "C38") (pin "2") (pinfunction "2_2") (pintype "passive"))
      (node (ref "C4") (pin "1") (pinfunction "1_1") (pintype "passive"))
      (node (ref "C40") (pin "1") (pinfunction "1_1") (pintype "passive"))
      (node (ref "C43") (pin "1") (pinfunction "1_1") (pintype "passive"))
      (node (ref "C47") (pin "1") (pinfunction "1_1") (pintype "passive"))
      (node (ref "C52") (pin "1") (pinfunction "1_1") (pintype "passive"))
      (node (ref "C6") (pin "1") (pinfunction "1_1") (pintype "passive"))
      (node (ref "C60") (pin "1") (pinfunction "1_1") (pintype "passive"))
      (node (ref "C64") (pin "2") (pinfunction "2_2") (pintype "passive"))
      (node (ref "C66") (pin "2") (pinfunction "2_2") (pintype "passive"))
      (node (ref "C67") (pin "2") (pinfunction "2_2") (pintype "passive"))
      (node (ref "C69") (pin "2") (pinfunction "2_2") (pintype "passive"))
      (node (ref "C8") (pin "1") (pinfunction "1_1") (pintype "passive"))
      (node (ref "D1") (pin "C") (pinfunction "C_C") (pintype "passive"))
      (node (ref "D2") (pin "C") (pinfunction "C_C") (pintype "passive"))
      (node (ref "D3") (pin "C") (pinfunction "C_C") (pintype "passive"))
      (node (ref "D5") (pin "C") (pinfunction "C_C") (pintype "passive"))
      (node (ref "F1") (pin "P$3") (pinfunction "2_P$3") (pintype "passive"))
      (node (ref "F1") (pin "P$4") (pinfunction "2_P$4") (pintype "passive"))
      (node (ref "IC1") (pin "16") (pinfunction "VS_16") (pintype "bidirectional"))
      (node (ref "IC1") (pin "30") (pinfunction "VSA_30") (pintype "bidirectional"))
      (node (ref "IC1") (pin "31") (pinfunction "VS_31") (pintype "bidirectional"))
      (node (ref "IC12") (pin "16") (pinfunction "VS_16") (pintype "bidirectional"))
      (node (ref "IC12") (pin "30") (pinfunction "VSA_30") (pintype "bidirectional"))
      (node (ref "IC12") (pin "31") (pinfunction "VS_31") (pintype "bidirectional"))
      (node (ref "IC15") (pin "16") (pinfunction "VS_16") (pintype "bidirectional"))
      (node (ref "IC15") (pin "30") (pinfunction "VSA_30") (pintype "bidirectional"))
      (node (ref "IC15") (pin "31") (pinfunction "VS_31") (pintype "bidirectional"))
      (node (ref "IC2") (pin "16") (pinfunction "VS_16") (pintype "bidirectional"))
      (node (ref "IC2") (pin "30") (pinfunction "VSA_30") (pintype "bidirectional"))
      (node (ref "IC2") (pin "31") (pinfunction "VS_31") (pintype "bidirectional"))
      (node (ref "IC5") (pin "16") (pinfunction "VS_16") (pintype "bidirectional"))
      (node (ref "IC5") (pin "30") (pinfunction "VSA_30") (pintype "bidirectional"))
      (node (ref "IC5") (pin "31") (pinfunction "VS_31") (pintype "bidirectional"))
      (node (ref "R14") (pin "2") (pinfunction "2_2") (pintype "passive"))
      (node (ref "R15") (pin "2") (pinfunction "2_2") (pintype "passive"))
      (node (ref "R16") (pin "2") (pinfunction "2_2") (pintype "passive"))
      (node (ref "R45") (pin "1") (pinfunction "1_1") (pintype "passive"))
      (node (ref "R55") (pin "2") (pinfunction "2_2") (pintype "passive"))
      (node (ref "R56") (pin "2") (pinfunction "2_2") (pintype "passive"))
      (node (ref "R57") (pin "2") (pinfunction "2_2") (pintype "passive"))
      (node (ref "U10") (pin "4") (pinfunction "VIN_4") (pintype "power_in"))
      (node (ref "U6") (pin "4") (pinfunction "VIN_4") (pintype "power_in"))
      (node (ref "X20") (pin "1") (pinfunction "1_1") (pintype "passive"))
      (node (ref "X20") (pin "2") (pinfunction "1_2") (pintype "passive"))
      (node (ref "X21") (pin "1") (pinfunction "1_1") (pintype "passive"))
      (node (ref "X3") (pin "1") (pinfunction "1_1") (pintype "passive"))
    )
    (net (code "65") (name "/VIN") (class "Default")
      (node (ref "F1") (pin "P$1") (pinfunction "1_P$1") (pintype "passive"))
      (node (ref "F1") (pin "P$2") (pinfunction "1_P$2") (pintype "passive"))
      (node (ref "LED8") (pin "A") (pinfunction "A_A") (pintype "passive"))
      (node (ref "X2") (pin "3") (pinfunction "1_3") (pintype "passive"))
      (node (ref "X2") (pin "4") (pinfunction "1_4") (pintype "passive"))
    )
    (net (code "66") (name "GND") (class "Default")
      (node (ref "C10") (pin "2") (pinfunction "2_2") (pintype "passive"))
      (node (ref "C11") (pin "2") (pinfunction "2_2") (pintype "passive"))
      (node (ref "C12") (pin "2") (pinfunction "2_2") (pintype "passive"))
      (node (ref "C13") (pin "2") (pinfunction "2_2") (pintype "passive"))
      (node (ref "C14") (pin "2") (pinfunction "2_2") (pintype "passive"))
      (node (ref "C15") (pin "2") (pinfunction "2_2") (pintype "passive"))
      (node (ref "C16") (pin "2") (pinfunction "2_2") (pintype "passive"))
      (node (ref "C17") (pin "2") (pinfunction "2_2") (pintype "passive"))
      (node (ref "C18") (pin "2") (pinfunction "2_2") (pintype "passive"))
      (node (ref "C19") (pin "2") (pinfunction "2_2") (pintype "passive"))
      (node (ref "C2") (pin "2") (pinfunction "2_2") (pintype "passive"))
      (node (ref "C20") (pin "1") (pinfunction "1_1") (pintype "passive"))
      (node (ref "C21") (pin "1") (pinfunction "1_1") (pintype "passive"))
      (node (ref "C23") (pin "2") (pinfunction "2_2") (pintype "passive"))
      (node (ref "C24") (pin "2") (pinfunction "2_2") (pintype "passive"))
      (node (ref "C25") (pin "2") (pinfunction "2_2") (pintype "passive"))
      (node (ref "C26") (pin "2") (pinfunction "2_2") (pintype "passive"))
      (node (ref "C27") (pin "2") (pinfunction "2_2") (pintype "passive"))
      (node (ref "C28") (pin "1") (pinfunction "1_1") (pintype "passive"))
      (node (ref "C29") (pin "2") (pinfunction "2_2") (pintype "passive"))
      (node (ref "C30") (pin "2") (pinfunction "2_2") (pintype "passive"))
      (node (ref "C31") (pin "2") (pinfunction "2_2") (pintype "passive"))
      (node (ref "C32") (pin "1") (pinfunction "1_1") (pintype "passive"))
      (node (ref "C33") (pin "1") (pinfunction "1_1") (pintype "passive"))
      (node (ref "C34") (pin "2") (pinfunction "2_2") (pintype "passive"))
      (node (ref "C36") (pin "2") (pinfunction "2_2") (pintype "passive"))
      (node (ref "C37") (pin "1") (pinfunction "1_1") (pintype "passive"))
      (node (ref "C4") (pin "2") (pinfunction "2_2") (pintype "passive"))
      (node (ref "C40") (pin "2") (pinfunction "2_2") (pintype "passive"))
      (node (ref "C41") (pin "2") (pinfunction "2_2") (pintype "passive"))
      (node (ref "C42") (pin "2") (pinfunction "2_2") (pintype "passive"))
      (node (ref "C43") (pin "2") (pinfunction "2_2") (pintype "passive"))
      (node (ref "C44") (pin "2") (pinfunction "2_2") (pintype "passive"))
      (node (ref "C45") (pin "2") (pinfunction "2_2") (pintype "passive"))
      (node (ref "C46") (pin "2") (pinfunction "2_2") (pintype "passive"))
      (node (ref "C47") (pin "2") (pinfunction "2_2") (pintype "passive"))
      (node (ref "C48") (pin "2") (pinfunction "2_2") (pintype "passive"))
      (node (ref "C49") (pin "2") (pinfunction "2_2") (pintype "passive"))
      (node (ref "C5") (pin "2") (pinfunction "2_2") (pintype "passive"))
      (node (ref "C52") (pin "2") (pinfunction "2_2") (pintype "passive"))
      (node (ref "C53") (pin "2") (pinfunction "2_2") (pintype "passive"))
      (node (ref "C54") (pin "2") (pinfunction "2_2") (pintype "passive"))
      (node (ref "C57") (pin "2") (pinfunction "2_2") (pintype "passive"))
      (node (ref "C58") (pin "2") (pinfunction "2_2") (pintype "passive"))
      (node (ref "C59") (pin "2") (pinfunction "2_2") (pintype "passive"))
      (node (ref "C6") (pin "2") (pinfunction "2_2") (pintype "passive"))
      (node (ref "C60") (pin "2") (pinfunction "2_2") (pintype "passive"))
      (node (ref "C61") (pin "2") (pinfunction "2_2") (pintype "passive"))
      (node (ref "C62") (pin "2") (pinfunction "2_2") (pintype "passive"))
      (node (ref "C63") (pin "2") (pinfunction "2_2") (pintype "passive"))
      (node (ref "C64") (pin "1") (pinfunction "1_1") (pintype "passive"))
      (node (ref "C65") (pin "1") (pinfunction "1_1") (pintype "passive"))
      (node (ref "C67") (pin "1") (pinfunction "1_1") (pintype "passive"))
      (node (ref "C68") (pin "1") (pinfunction "1_1") (pintype "passive"))
      (node (ref "C70") (pin "2") (pinfunction "2_2") (pintype "passive"))
      (node (ref "C71") (pin "2") (pinfunction "2_2") (pintype "passive"))
      (node (ref "C72") (pin "2") (pinfunction "2_2") (pintype "passive"))
      (node (ref "C73") (pin "2") (pinfunction "2_2") (pintype "passive"))
      (node (ref "C74") (pin "2") (pinfunction "2_2") (pintype "passive"))
      (node (ref "C75") (pin "2") (pinfunction "2_2") (pintype "passive"))
      (node (ref "C76") (pin "2") (pinfunction "2_2") (pintype "passive"))
      (node (ref "C77") (pin "2") (pinfunction "2_2") (pintype "passive"))
      (node (ref "C78") (pin "2") (pinfunction "2_2") (pintype "passive"))
      (node (ref "C79") (pin "2") (pinfunction "2_2") (pintype "passive"))
      (node (ref "C8") (pin "2") (pinfunction "2_2") (pintype "passive"))
      (node (ref "C80") (pin "2") (pinfunction "2_2") (pintype "passive"))
      (node (ref "C81") (pin "2") (pinfunction "2_2") (pintype "passive"))
      (node (ref "C82") (pin "2") (pinfunction "2_2") (pintype "passive"))
      (node (ref "C83") (pin "2") (pinfunction "2_2") (pintype "passive"))
      (node (ref "C84") (pin "2") (pinfunction "2_2") (pintype "passive"))
      (node (ref "C85") (pin "2") (pinfunction "2_2") (pintype "passive"))
      (node (ref "C86") (pin "2") (pinfunction "2_2") (pintype "passive"))
      (node (ref "C87") (pin "2") (pinfunction "2_2") (pintype "passive"))
      (node (ref "C88") (pin "2") (pinfunction "2_2") (pintype "passive"))
      (node (ref "D4") (pin "A") (pinfunction "A_A") (pintype "passive"))
      (node (ref "D5") (pin "A") (pinfunction "A_A") (pintype "passive"))
      (node (ref "D6") (pin "A") (pinfunction "A_A") (pintype "passive"))
      (node (ref "IC1") (pin "1") (pinfunction "CLK_1") (pintype "bidirectional"))
      (node (ref "IC1") (pin "10") (pinfunction "SPI_MODE_10") (pintype "bidirectional"))
      (node (ref "IC1") (pin "11") (pinfunction "GND_11") (pintype "bidirectional"))
      (node (ref "IC1") (pin "12") (pinfunction "GND_12") (pintype "bidirectional"))
      (node (ref "IC1") (pin "24") (pinfunction "GNDA_24") (pintype "bidirectional"))
      (node (ref "IC1") (pin "35") (pinfunction "GND_35") (pintype "bidirectional"))
      (node (ref "IC1") (pin "36") (pinfunction "TST_MODE_36") (pintype "bidirectional"))
      (node (ref "IC1") (pin "TP") (pinfunction "GND_TP") (pintype "bidirectional"))
      (node (ref "IC10") (pin "3") (pinfunction "GND_3") (pintype "power_in"))
      (node (ref "IC11") (pin "3") (pinfunction "GND_3") (pintype "power_in"))
      (node (ref "IC12") (pin "1") (pinfunction "CLK_1") (pintype "bidirectional"))
      (node (ref "IC12") (pin "10") (pinfunction "SPI_MODE_10") (pintype "bidirectional"))
      (node (ref "IC12") (pin "11") (pinfunction "GND_11") (pintype "bidirectional"))
      (node (ref "IC12") (pin "12") (pinfunction "GND_12") (pintype "bidirectional"))
      (node (ref "IC12") (pin "24") (pinfunction "GNDA_24") (pintype "bidirectional"))
      (node (ref "IC12") (pin "35") (pinfunction "GND_35") (pintype "bidirectional"))
      (node (ref "IC12") (pin "36") (pinfunction "TST_MODE_36") (pintype "bidirectional"))
      (node (ref "IC12") (pin "TP") (pinfunction "GND_TP") (pintype "bidirectional"))
      (node (ref "IC13") (pin "3") (pinfunction "GND_3") (pintype "power_in"))
      (node (ref "IC14") (pin "3") (pinfunction "GND_3") (pintype "power_in"))
      (node (ref "IC15") (pin "1") (pinfunction "CLK_1") (pintype "bidirectional"))
      (node (ref "IC15") (pin "10") (pinfunction "SPI_MODE_10") (pintype "bidirectional"))
      (node (ref "IC15") (pin "11") (pinfunction "GND_11") (pintype "bidirectional"))
      (node (ref "IC15") (pin "12") (pinfunction "GND_12") (pintype "bidirectional"))
      (node (ref "IC15") (pin "24") (pinfunction "GNDA_24") (pintype "bidirectional"))
      (node (ref "IC15") (pin "35") (pinfunction "GND_35") (pintype "bidirectional"))
      (node (ref "IC15") (pin "36") (pinfunction "TST_MODE_36") (pintype "bidirectional"))
      (node (ref "IC15") (pin "TP") (pinfunction "GND_TP") (pintype "bidirectional"))
      (node (ref "IC16") (pin "3") (pinfunction "GND_3") (pintype "power_in"))
      (node (ref "IC17") (pin "3") (pinfunction "GND_3") (pintype "power_in"))
      (node (ref "IC2") (pin "1") (pinfunction "CLK_1") (pintype "bidirectional"))
      (node (ref "IC2") (pin "10") (pinfunction "SPI_MODE_10") (pintype "bidirectional"))
      (node (ref "IC2") (pin "11") (pinfunction "GND_11") (pintype "bidirectional"))
      (node (ref "IC2") (pin "12") (pinfunction "GND_12") (pintype "bidirectional"))
      (node (ref "IC2") (pin "24") (pinfunction "GNDA_24") (pintype "bidirectional"))
      (node (ref "IC2") (pin "35") (pinfunction "GND_35") (pintype "bidirectional"))
      (node (ref "IC2") (pin "36") (pinfunction "TST_MODE_36") (pintype "bidirectional"))
      (node (ref "IC2") (pin "TP") (pinfunction "GND_TP") (pintype "bidirectional"))
      (node (ref "IC3") (pin "3") (pinfunction "GND_3") (pintype "power_in"))
      (node (ref "IC4") (pin "3") (pinfunction "GND_3") (pintype "power_in"))
      (node (ref "IC5") (pin "1") (pinfunction "CLK_1") (pintype "bidirectional"))
      (node (ref "IC5") (pin "10") (pinfunction "SPI_MODE_10") (pintype "bidirectional"))
      (node (ref "IC5") (pin "11") (pinfunction "GND_11") (pintype "bidirectional"))
      (node (ref "IC5") (pin "12") (pinfunction "GND_12") (pintype "bidirectional"))
      (node (ref "IC5") (pin "24") (pinfunction "GNDA_24") (pintype "bidirectional"))
      (node (ref "IC5") (pin "35") (pinfunction "GND_35") (pintype "bidirectional"))
      (node (ref "IC5") (pin "36") (pinfunction "TST_MODE_36") (pintype "bidirectional"))
      (node (ref "IC5") (pin "TP") (pinfunction "GND_TP") (pintype "bidirectional"))
      (node (ref "IC6") (pin "3") (pinfunction "GND_3") (pintype "power_in"))
      (node (ref "IC7") (pin "3") (pinfunction "GND_3") (pintype "power_in"))
      (node (ref "IC8") (pin "3") (pinfunction "GND_3") (pintype "power_in"))
      (node (ref "IC9") (pin "3") (pinfunction "GND_3") (pintype "power_in"))
      (node (ref "LED4") (pin "C") (pinfunction "C_C") (pintype "passive"))
      (node (ref "P8") (pin "1") (pinfunction "1_1") (pintype "passive"))
      (node (ref "P8") (pin "2") (pinfunction "2_2") (pintype "passive"))
      (node (ref "P9") (pin "1") (pinfunction "1_1") (pintype "passive"))
      (node (ref "P9") (pin "2") (pinfunction "2_2") (pintype "passive"))
      (node (ref "P9") (pin "43") (pinfunction "43_43") (pintype "passive"))
      (node (ref "P9") (pin "44") (pinfunction "44_44") (pintype "passive"))
      (node (ref "P9") (pin "45") (pinfunction "45_45") (pintype "passive"))
      (node (ref "P9") (pin "46") (pinfunction "46_46") (pintype "passive"))
      (node (ref "Q1") (pin "1") (pinfunction "S_1") (pintype "passive"))
      (node (ref "Q1") (pin "2") (pinfunction "S_2") (pintype "passive"))
      (node (ref "Q1") (pin "3") (pinfunction "S_3") (pintype "passive"))
      (node (ref "Q2") (pin "1") (pinfunction "S_1") (pintype "passive"))
      (node (ref "Q2") (pin "2") (pinfunction "S_2") (pintype "passive"))
      (node (ref "Q2") (pin "3") (pinfunction "S_3") (pintype "passive"))
      (node (ref "Q3") (pin "1") (pinfunction "S_1") (pintype "passive"))
      (node (ref "Q3") (pin "2") (pinfunction "S_2") (pintype "passive"))
      (node (ref "Q3") (pin "3") (pinfunction "S_3") (pintype "passive"))
      (node (ref "Q4") (pin "2") (pinfunction "E_2") (pintype "passive"))
      (node (ref "Q5") (pin "2") (pinfunction "E_2") (pintype "passive"))
      (node (ref "Q6") (pin "2") (pinfunction "E_2") (pintype "passive"))
      (node (ref "Q7") (pin "2") (pinfunction "E_2") (pintype "passive"))
      (node (ref "R1") (pin "1") (pinfunction "1_1") (pintype "passive"))
      (node (ref "R10") (pin "1") (pinfunction "1_1") (pintype "passive"))
      (node (ref "R2") (pin "1") (pinfunction "1_1") (pintype "passive"))
      (node (ref "R22") (pin "2") (pinfunction "2_2") (pintype "passive"))
      (node (ref "R26") (pin "2") (pinfunction "2_2") (pintype "passive"))
      (node (ref "R29") (pin "1") (pinfunction "1_1") (pintype "passive"))
      (node (ref "R3") (pin "1") (pinfunction "1_1") (pintype "passive"))
      (node (ref "R30") (pin "1") (pinfunction "1_1") (pintype "passive"))
      (node (ref "R32") (pin "1") (pinfunction "1_1") (pintype "passive"))
      (node (ref "R33") (pin "1") (pinfunction "1_1") (pintype "passive"))
      (node (ref "R34") (pin "1") (pinfunction "1_1") (pintype "passive"))
      (node (ref "R4") (pin "1") (pinfunction "1_1") (pintype "passive"))
      (node (ref "R43") (pin "2") (pinfunction "2_2") (pintype "passive"))
      (node (ref "R44") (pin "2") (pinfunction "2_2") (pintype "passive"))
      (node (ref "R46") (pin "1") (pinfunction "1_1") (pintype "passive"))
      (node (ref "R47") (pin "1") (pinfunction "1_1") (pintype "passive"))
      (node (ref "R48") (pin "1") (pinfunction "1_1") (pintype "passive"))
      (node (ref "R5") (pin "1") (pinfunction "1_1") (pintype "passive"))
      (node (ref "R7") (pin "1") (pinfunction "1_1") (pintype "passive"))
      (node (ref "R8") (pin "1") (pinfunction "1_1") (pintype "passive"))
      (node (ref "R9") (pin "1") (pinfunction "1_1") (pintype "passive"))
      (node (ref "U1") (pin "13") (pinfunction "~{OE}_13") (pintype "input"))
      (node (ref "U1") (pin "8") (pinfunction "GND_8") (pintype "passive"))
      (node (ref "U10") (pin "6") (pinfunction "GND_6") (pintype "power_in"))
      (node (ref "U10") (pin "EP") (pinfunction "EP_EP") (pintype "power_in"))
      (node (ref "U11") (pin "14") (pinfunction "VSS_14") (pintype "passive"))
      (node (ref "U18") (pin "1") (pinfunction "A0_1") (pintype "input"))
      (node (ref "U18") (pin "2") (pinfunction "A1_2") (pintype "input"))
      (node (ref "U18") (pin "4") (pinfunction "GND_4") (pintype "power_in"))
      (node (ref "U19") (pin "8") (pinfunction "VSS_8") (pintype "power_in"))
      (node (ref "U2") (pin "13") (pinfunction "~{OE}_13") (pintype "input"))
      (node (ref "U2") (pin "8") (pinfunction "GND_8") (pintype "passive"))
      (node (ref "U3") (pin "13") (pinfunction "~{OE}_13") (pintype "input"))
      (node (ref "U3") (pin "8") (pinfunction "GND_8") (pintype "passive"))
      (node (ref "U4") (pin "13") (pinfunction "~{OE}_13") (pintype "input"))
      (node (ref "U4") (pin "8") (pinfunction "GND_8") (pintype "passive"))
      (node (ref "U5") (pin "13") (pinfunction "~{OE}_13") (pintype "input"))
      (node (ref "U5") (pin "8") (pinfunction "GND_8") (pintype "passive"))
      (node (ref "U6") (pin "6") (pinfunction "GND_6") (pintype "power_in"))
      (node (ref "U6") (pin "EP") (pinfunction "EP_EP") (pintype "power_in"))
      (node (ref "X1") (pin "3") (pinfunction "S_3") (pintype "passive"))
      (node (ref "X10") (pin "3") (pinfunction "S_3") (pintype "passive"))
      (node (ref "X11") (pin "1") (pinfunction "S_1") (pintype "passive"))
      (node (ref "X12") (pin "3") (pinfunction "S_3") (pintype "passive"))
      (node (ref "X13") (pin "3") (pinfunction "S_3") (pintype "passive"))
      (node (ref "X19") (pin "3") (pinfunction "S_3") (pintype "passive"))
      (node (ref "X2") (pin "1") (pinfunction "1_1") (pintype "passive"))
      (node (ref "X2") (pin "2") (pinfunction "1_2") (pintype "passive"))
      (node (ref "X22") (pin "3") (pinfunction "S_3") (pintype "passive"))
      (node (ref "X23") (pin "3") (pinfunction "S_3") (pintype "passive"))
      (node (ref "X7") (pin "1") (pinfunction "S_1") (pintype "passive"))
      (node (ref "X8") (pin "1") (pinfunction "S_1") (pintype "passive"))
    )
    (net (code "67") (name "Net-(C51-Pad2)") (class "Default")
      (node (ref "C51") (pin "2") (pinfunction "2_2") (pintype "passive"))
      (node (ref "R26") (pin "1") (pinfunction "1_1") (pintype "passive"))
    )
    (net (code "68") (name "Net-(C56-Pad2)") (class "Default")
      (node (ref "C56") (pin "2") (pinfunction "2_2") (pintype "passive"))
      (node (ref "R44") (pin "1") (pinfunction "1_1") (pintype "passive"))
    )
    (net (code "69") (name "Net-(C75-Pad1)") (class "Default")
      (node (ref "C75") (pin "1") (pinfunction "1_1") (pintype "passive"))
      (node (ref "R31") (pin "1") (pinfunction "1_1") (pintype "passive"))
      (node (ref "R50") (pin "2") (pinfunction "2_2") (pintype "passive"))
    )
    (net (code "70") (name "Net-(C76-Pad1)") (class "Default")
      (node (ref "C76") (pin "1") (pinfunction "1_1") (pintype "passive"))
      (node (ref "R37") (pin "1") (pinfunction "1_1") (pintype "passive"))
      (node (ref "R6") (pin "2") (pinfunction "2_2") (pintype "passive"))
    )
    (net (code "71") (name "Net-(C77-Pad1)") (class "Default")
      (node (ref "C77") (pin "1") (pinfunction "1_1") (pintype "passive"))
      (node (ref "R41") (pin "1") (pinfunction "1_1") (pintype "passive"))
      (node (ref "R49") (pin "2") (pinfunction "2_2") (pintype "passive"))
    )
    (net (code "72") (name "Net-(C78-Pad1)") (class "Default")
      (node (ref "C78") (pin "1") (pinfunction "1_1") (pintype "passive"))
      (node (ref "R27") (pin "2") (pinfunction "2_2") (pintype "passive"))
      (node (ref "R58") (pin "1") (pinfunction "1_1") (pintype "passive"))
    )
    (net (code "73") (name "Net-(C79-Pad1)") (class "Default")
      (node (ref "C79") (pin "1") (pinfunction "1_1") (pintype "passive"))
      (node (ref "R35") (pin "2") (pinfunction "2_2") (pintype "passive"))
      (node (ref "R60") (pin "1") (pinfunction "1_1") (pintype "passive"))
    )
    (net (code "74") (name "Net-(IC1-5VOUT)") (class "Default")
      (node (ref "C21") (pin "2") (pinfunction "2_2") (pintype "passive"))
      (node (ref "IC1") (pin "25") (pinfunction "5VOUT_25") (pintype "bidirectional"))
      (node (ref "R53") (pin "1") (pinfunction "1_1") (pintype "passive"))
    )
    (net (code "75") (name "Net-(IC1-AIN_IREF)") (class "Default")
      (node (ref "C12") (pin "1") (pinfunction "1_1") (pintype "passive"))
      (node (ref "IC1") (pin "23") (pinfunction "AIN_IREF_23") (pintype "bidirectional"))
      (node (ref "R49") (pin "1") (pinfunction "1_1") (pintype "passive"))
    )
    (net (code "76") (name "Net-(IC1-BRA)") (class "Default")
      (node (ref "IC1") (pin "33") (pinfunction "BRA_33") (pintype "bidirectional"))
      (node (ref "R2") (pin "2") (pinfunction "2_2") (pintype "passive"))
    )
    (net (code "77") (name "Net-(IC1-BRB)") (class "Default")
      (node (ref "IC1") (pin "14") (pinfunction "BRB_14") (pintype "bidirectional"))
      (node (ref "R1") (pin "2") (pinfunction "2_2") (pintype "passive"))
    )
    (net (code "78") (name "Net-(IC1-CPI)") (class "Default")
      (node (ref "C1") (pin "1") (pinfunction "1_1") (pintype "passive"))
      (node (ref "IC1") (pin "28") (pinfunction "CPI_28") (pintype "bidirectional"))
    )
    (net (code "79") (name "Net-(IC1-CPO)") (class "Default")
      (node (ref "C1") (pin "2") (pinfunction "2_2") (pintype "passive"))
      (node (ref "IC1") (pin "27") (pinfunction "CPO_27") (pintype "bidirectional"))
    )
    (net (code "80") (name "Net-(IC1-ENCA_DCIN_CFG5)") (class "Default")
      (node (ref "IC1") (pin "19") (pinfunction "ENCA_DCIN_CFG5_19") (pintype "bidirectional"))
      (node (ref "U1") (pin "1") (pinfunction "QB_1") (pintype "output"))
    )
    (net (code "81") (name "Net-(IC1-ENCB_DCEN_CFG4)") (class "Default")
      (node (ref "IC1") (pin "18") (pinfunction "ENCB_DCEN_CFG4_18") (pintype "bidirectional"))
      (node (ref "U1") (pin "2") (pinfunction "QC_2") (pintype "output"))
    )
    (net (code "82") (name "Net-(IC1-OA1)") (class "Default")
      (node (ref "IC1") (pin "34") (pinfunction "OA1_34") (pintype "bidirectional"))
      (node (ref "X14") (pin "2") (pinfunction "S_2") (pintype "passive"))
    )
    (net (code "83") (name "Net-(IC1-OA2)") (class "Default")
      (node (ref "IC1") (pin "32") (pinfunction "OA2_32") (pintype "bidirectional"))
      (node (ref "X14") (pin "3") (pinfunction "S_3") (pintype "passive"))
    )
    (net (code "84") (name "Net-(IC1-OB1)") (class "Default")
      (node (ref "IC1") (pin "13") (pinfunction "OB1_13") (pintype "bidirectional"))
      (node (ref "X14") (pin "1") (pinfunction "S_1") (pintype "passive"))
    )
    (net (code "85") (name "Net-(IC1-OB2)") (class "Default")
      (node (ref "IC1") (pin "15") (pinfunction "OB2_15") (pintype "bidirectional"))
      (node (ref "X14") (pin "4") (pinfunction "S_4") (pintype "passive"))
    )
    (net (code "86") (name "Net-(IC1-SCK_CFG2)") (class "Default")
      (node (ref "IC1") (pin "3") (pinfunction "SCK_CFG2_3") (pintype "bidirectional"))
      (node (ref "IC3") (pin "4") (pinfunction "O_4") (pintype "output"))
    )
    (net (code "87") (name "Net-(IC1-SDI_NAI_CFG1)") (class "Default")
      (node (ref "IC1") (pin "4") (pinfunction "SDI_NAI_CFG1_4") (pintype "bidirectional"))
      (node (ref "IC4") (pin "4") (pinfunction "O_4") (pintype "output"))
    )
    (net (code "88") (name "Net-(IC1-SDO_NAO_CFG0)") (class "Default")
      (node (ref "IC1") (pin "5") (pinfunction "SDO_NAO_CFG0_5") (pintype "bidirectional"))
      (node (ref "U1") (pin "3") (pinfunction "QD_3") (pintype "output"))
    )
    (net (code "89") (name "Net-(IC1-VCC)") (class "Default")
      (node (ref "C71") (pin "1") (pinfunction "1_1") (pintype "passive"))
      (node (ref "IC1") (pin "26") (pinfunction "VCC_26") (pintype "bidirectional"))
      (node (ref "R53") (pin "2") (pinfunction "2_2") (pintype "passive"))
    )
    (net (code "90") (name "Net-(IC1-VCP)") (class "Default")
      (node (ref "C22") (pin "1") (pinfunction "1_1") (pintype "passive"))
      (node (ref "IC1") (pin "29") (pinfunction "VCP_29") (pintype "bidirectional"))
    )
    (net (code "91") (name "Net-(IC2-5VOUT)") (class "Default")
      (node (ref "C33") (pin "2") (pinfunction "2_2") (pintype "passive"))
      (node (ref "IC2") (pin "25") (pinfunction "5VOUT_25") (pintype "bidirectional"))
      (node (ref "R59") (pin "1") (pinfunction "1_1") (pintype "passive"))
    )
    (net (code "92") (name "Net-(IC2-AIN_IREF)") (class "Default")
      (node (ref "C18") (pin "1") (pinfunction "1_1") (pintype "passive"))
      (node (ref "IC2") (pin "23") (pinfunction "AIN_IREF_23") (pintype "bidirectional"))
      (node (ref "R6") (pin "1") (pinfunction "1_1") (pintype "passive"))
    )
    (net (code "93") (name "Net-(IC2-BRA)") (class "Default")
      (node (ref "IC2") (pin "33") (pinfunction "BRA_33") (pintype "bidirectional"))
      (node (ref "R4") (pin "2") (pinfunction "2_2") (pintype "passive"))
    )
    (net (code "94") (name "Net-(IC2-BRB)") (class "Default")
      (node (ref "IC2") (pin "14") (pinfunction "BRB_14") (pintype "bidirectional"))
      (node (ref "R3") (pin "2") (pinfunction "2_2") (pintype "passive"))
    )
    (net (code "95") (name "Net-(IC2-CPI)") (class "Default")
      (node (ref "C3") (pin "1") (pinfunction "1_1") (pintype "passive"))
      (node (ref "IC2") (pin "28") (pinfunction "CPI_28") (pintype "bidirectional"))
    )
    (net (code "96") (name "Net-(IC2-CPO)") (class "Default")
      (node (ref "C3") (pin "2") (pinfunction "2_2") (pintype "passive"))
      (node (ref "IC2") (pin "27") (pinfunction "CPO_27") (pintype "bidirectional"))
    )
    (net (code "97") (name "Net-(IC2-ENCA_DCIN_CFG5)") (class "Default")
      (node (ref "IC2") (pin "19") (pinfunction "ENCA_DCIN_CFG5_19") (pintype "bidirectional"))
      (node (ref "U2") (pin "1") (pinfunction "QB_1") (pintype "output"))
    )
    (net (code "98") (name "Net-(IC2-ENCB_DCEN_CFG4)") (class "Default")
      (node (ref "IC2") (pin "18") (pinfunction "ENCB_DCEN_CFG4_18") (pintype "bidirectional"))
      (node (ref "U2") (pin "2") (pinfunction "QC_2") (pintype "output"))
    )
    (net (code "99") (name "Net-(IC2-OA1)") (class "Default")
      (node (ref "IC2") (pin "34") (pinfunction "OA1_34") (pintype "bidirectional"))
      (node (ref "X15") (pin "2") (pinfunction "S_2") (pintype "passive"))
    )
    (net (code "100") (name "Net-(IC2-OA2)") (class "Default")
      (node (ref "IC2") (pin "32") (pinfunction "OA2_32") (pintype "bidirectional"))
      (node (ref "X15") (pin "3") (pinfunction "S_3") (pintype "passive"))
    )
    (net (code "101") (name "Net-(IC2-OB1)") (class "Default")
      (node (ref "IC2") (pin "13") (pinfunction "OB1_13") (pintype "bidirectional"))
      (node (ref "X15") (pin "1") (pinfunction "S_1") (pintype "passive"))
    )
    (net (code "102") (name "Net-(IC2-OB2)") (class "Default")
      (node (ref "IC2") (pin "15") (pinfunction "OB2_15") (pintype "bidirectional"))
      (node (ref "X15") (pin "4") (pinfunction "S_4") (pintype "passive"))
    )
    (net (code "103") (name "Net-(IC2-SCK_CFG2)") (class "Default")
      (node (ref "IC2") (pin "3") (pinfunction "SCK_CFG2_3") (pintype "bidirectional"))
      (node (ref "IC8") (pin "4") (pinfunction "O_4") (pintype "output"))
    )
    (net (code "104") (name "Net-(IC2-SDI_NAI_CFG1)") (class "Default")
      (node (ref "IC2") (pin "4") (pinfunction "SDI_NAI_CFG1_4") (pintype "bidirectional"))
      (node (ref "IC9") (pin "4") (pinfunction "O_4") (pintype "output"))
    )
    (net (code "105") (name "Net-(IC2-SDO_NAO_CFG0)") (class "Default")
      (node (ref "IC2") (pin "5") (pinfunction "SDO_NAO_CFG0_5") (pintype "bidirectional"))
      (node (ref "U2") (pin "3") (pinfunction "QD_3") (pintype "output"))
    )
    (net (code "106") (name "Net-(IC2-VCC)") (class "Default")
      (node (ref "C72") (pin "1") (pinfunction "1_1") (pintype "passive"))
      (node (ref "IC2") (pin "26") (pinfunction "VCC_26") (pintype "bidirectional"))
      (node (ref "R59") (pin "2") (pinfunction "2_2") (pintype "passive"))
    )
    (net (code "107") (name "Net-(IC2-VCP)") (class "Default")
      (node (ref "C35") (pin "1") (pinfunction "1_1") (pintype "passive"))
      (node (ref "IC2") (pin "29") (pinfunction "VCP_29") (pintype "bidirectional"))
    )
    (net (code "108") (name "Net-(IC3A-I)") (class "Default")
      (node (ref "IC3") (pin "2") (pinfunction "I_2") (pintype "input"))
      (node (ref "U1") (pin "4") (pinfunction "QE_4") (pintype "output"))
    )
    (net (code "109") (name "Net-(IC3A-OE)") (class "Default")
      (node (ref "IC3") (pin "1") (pinfunction "OE_1") (pintype "input"))
      (node (ref "U1") (pin "5") (pinfunction "QF_5") (pintype "output"))
    )
    (net (code "110") (name "Net-(IC4A-I)") (class "Default")
      (node (ref "IC4") (pin "2") (pinfunction "I_2") (pintype "input"))
      (node (ref "U1") (pin "6") (pinfunction "QG_6") (pintype "output"))
    )
    (net (code "111") (name "Net-(IC4A-OE)") (class "Default")
      (node (ref "IC4") (pin "1") (pinfunction "OE_1") (pintype "input"))
      (node (ref "U1") (pin "7") (pinfunction "QH_7") (pintype "output"))
    )
    (net (code "112") (name "Net-(IC5-5VOUT)") (class "Default")
      (node (ref "C37") (pin "2") (pinfunction "2_2") (pintype "passive"))
      (node (ref "IC5") (pin "25") (pinfunction "5VOUT_25") (pintype "bidirectional"))
      (node (ref "R70") (pin "1") (pinfunction "1_1") (pintype "passive"))
    )
    (net (code "113") (name "Net-(IC5-AIN_IREF)") (class "Default")
      (node (ref "C25") (pin "1") (pinfunction "1_1") (pintype "passive"))
      (node (ref "IC5") (pin "23") (pinfunction "AIN_IREF_23") (pintype "bidirectional"))
      (node (ref "R27") (pin "1") (pinfunction "1_1") (pintype "passive"))
    )
    (net (code "114") (name "Net-(IC5-BRA)") (class "Default")
      (node (ref "IC5") (pin "33") (pinfunction "BRA_33") (pintype "bidirectional"))
      (node (ref "R8") (pin "2") (pinfunction "2_2") (pintype "passive"))
    )
    (net (code "115") (name "Net-(IC5-BRB)") (class "Default")
      (node (ref "IC5") (pin "14") (pinfunction "BRB_14") (pintype "bidirectional"))
      (node (ref "R7") (pin "2") (pinfunction "2_2") (pintype "passive"))
    )
    (net (code "116") (name "Net-(IC5-CPI)") (class "Default")
      (node (ref "C7") (pin "1") (pinfunction "1_1") (pintype "passive"))
      (node (ref "IC5") (pin "28") (pinfunction "CPI_28") (pintype "bidirectional"))
    )
    (net (code "117") (name "Net-(IC5-CPO)") (class "Default")
      (node (ref "C7") (pin "2") (pinfunction "2_2") (pintype "passive"))
      (node (ref "IC5") (pin "27") (pinfunction "CPO_27") (pintype "bidirectional"))
    )
    (net (code "118") (name "Net-(IC5-ENCA_DCIN_CFG5)") (class "Default")
      (node (ref "IC5") (pin "19") (pinfunction "ENCA_DCIN_CFG5_19") (pintype "bidirectional"))
      (node (ref "U3") (pin "1") (pinfunction "QB_1") (pintype "output"))
    )
    (net (code "119") (name "Net-(IC5-ENCB_DCEN_CFG4)") (class "Default")
      (node (ref "IC5") (pin "18") (pinfunction "ENCB_DCEN_CFG4_18") (pintype "bidirectional"))
      (node (ref "U3") (pin "2") (pinfunction "QC_2") (pintype "output"))
    )
    (net (code "120") (name "Net-(IC5-OA1)") (class "Default")
      (node (ref "IC5") (pin "34") (pinfunction "OA1_34") (pintype "bidirectional"))
      (node (ref "X16") (pin "2") (pinfunction "S_2") (pintype "passive"))
    )
    (net (code "121") (name "Net-(IC5-OA2)") (class "Default")
      (node (ref "IC5") (pin "32") (pinfunction "OA2_32") (pintype "bidirectional"))
      (node (ref "X16") (pin "3") (pinfunction "S_3") (pintype "passive"))
    )
    (net (code "122") (name "Net-(IC5-OB1)") (class "Default")
      (node (ref "IC5") (pin "13") (pinfunction "OB1_13") (pintype "bidirectional"))
      (node (ref "X16") (pin "1") (pinfunction "S_1") (pintype "passive"))
    )
    (net (code "123") (name "Net-(IC5-OB2)") (class "Default")
      (node (ref "IC5") (pin "15") (pinfunction "OB2_15") (pintype "bidirectional"))
      (node (ref "X16") (pin "4") (pinfunction "S_4") (pintype "passive"))
    )
    (net (code "124") (name "Net-(IC5-SDO_NAO_CFG0)") (class "Default")
      (node (ref "IC5") (pin "5") (pinfunction "SDO_NAO_CFG0_5") (pintype "bidirectional"))
      (node (ref "U3") (pin "3") (pinfunction "QD_3") (pintype "output"))
    )
    (net (code "125") (name "Net-(IC5-VCC)") (class "Default")
      (node (ref "C73") (pin "1") (pinfunction "1_1") (pintype "passive"))
      (node (ref "IC5") (pin "26") (pinfunction "VCC_26") (pintype "bidirectional"))
      (node (ref "R70") (pin "2") (pinfunction "2_2") (pintype "passive"))
    )
    (net (code "126") (name "Net-(IC5-VCP)") (class "Default")
      (node (ref "C38") (pin "1") (pinfunction "1_1") (pintype "passive"))
      (node (ref "IC5") (pin "29") (pinfunction "VCP_29") (pintype "bidirectional"))
    )
    (net (code "127") (name "Net-(IC8A-I)") (class "Default")
      (node (ref "IC8") (pin "2") (pinfunction "I_2") (pintype "input"))
      (node (ref "U2") (pin "4") (pinfunction "QE_4") (pintype "output"))
    )
    (net (code "128") (name "Net-(IC8A-OE)") (class "Default")
      (node (ref "IC8") (pin "1") (pinfunction "OE_1") (pintype "input"))
      (node (ref "U2") (pin "5") (pinfunction "QF_5") (pintype "output"))
    )
    (net (code "129") (name "Net-(IC9A-I)") (class "Default")
      (node (ref "IC9") (pin "2") (pinfunction "I_2") (pintype "input"))
      (node (ref "U2") (pin "6") (pinfunction "QG_6") (pintype "output"))
    )
    (net (code "130") (name "Net-(IC9A-OE)") (class "Default")
      (node (ref "IC9") (pin "1") (pinfunction "OE_1") (pintype "input"))
      (node (ref "U2") (pin "7") (pinfunction "QH_7") (pintype "output"))
    )
    (net (code "131") (name "Net-(IC10A-I)") (class "Default")
      (node (ref "IC10") (pin "2") (pinfunction "I_2") (pintype "input"))
      (node (ref "U3") (pin "4") (pinfunction "QE_4") (pintype "output"))
    )
    (net (code "132") (name "Net-(IC10A-O)") (class "Default")
      (node (ref "IC10") (pin "4") (pinfunction "O_4") (pintype "output"))
      (node (ref "IC5") (pin "3") (pinfunction "SCK_CFG2_3") (pintype "bidirectional"))
    )
    (net (code "133") (name "Net-(IC10A-OE)") (class "Default")
      (node (ref "IC10") (pin "1") (pinfunction "OE_1") (pintype "input"))
      (node (ref "U3") (pin "5") (pinfunction "QF_5") (pintype "output"))
    )
    (net (code "134") (name "Net-(IC11A-I)") (class "Default")
      (node (ref "IC11") (pin "2") (pinfunction "I_2") (pintype "input"))
      (node (ref "U3") (pin "6") (pinfunction "QG_6") (pintype "output"))
    )
    (net (code "135") (name "Net-(IC11A-O)") (class "Default")
      (node (ref "IC11") (pin "4") (pinfunction "O_4") (pintype "output"))
      (node (ref "IC5") (pin "4") (pinfunction "SDI_NAI_CFG1_4") (pintype "bidirectional"))
    )
    (net (code "136") (name "Net-(IC11A-OE)") (class "Default")
      (node (ref "IC11") (pin "1") (pinfunction "OE_1") (pintype "input"))
      (node (ref "U3") (pin "7") (pinfunction "QH_7") (pintype "output"))
    )
    (net (code "137") (name "Net-(IC12-5VOUT)") (class "Default")
      (node (ref "C65") (pin "2") (pinfunction "2_2") (pintype "passive"))
      (node (ref "IC12") (pin "25") (pinfunction "5VOUT_25") (pintype "bidirectional"))
      (node (ref "R71") (pin "1") (pinfunction "1_1") (pintype "passive"))
    )
    (net (code "138") (name "Net-(IC12-AIN_IREF)") (class "Default")
      (node (ref "C62") (pin "1") (pinfunction "1_1") (pintype "passive"))
      (node (ref "IC12") (pin "23") (pinfunction "AIN_IREF_23") (pintype "bidirectional"))
      (node (ref "R35") (pin "1") (pinfunction "1_1") (pintype "passive"))
    )
    (net (code "139") (name "Net-(IC12-BRA)") (class "Default")
      (node (ref "IC12") (pin "33") (pinfunction "BRA_33") (pintype "bidirectional"))
      (node (ref "R30") (pin "2") (pinfunction "2_2") (pintype "passive"))
    )
    (net (code "140") (name "Net-(IC12-BRB)") (class "Default")
      (node (ref "IC12") (pin "14") (pinfunction "BRB_14") (pintype "bidirectional"))
      (node (ref "R29") (pin "2") (pinfunction "2_2") (pintype "passive"))
    )
    (net (code "141") (name "Net-(IC12-CPI)") (class "Default")
      (node (ref "C39") (pin "1") (pinfunction "1_1") (pintype "passive"))
      (node (ref "IC12") (pin "28") (pinfunction "CPI_28") (pintype "bidirectional"))
    )
    (net (code "142") (name "Net-(IC12-CPO)") (class "Default")
      (node (ref "C39") (pin "2") (pinfunction "2_2") (pintype "passive"))
      (node (ref "IC12") (pin "27") (pinfunction "CPO_27") (pintype "bidirectional"))
    )
    (net (code "143") (name "Net-(IC12-ENCA_DCIN_CFG5)") (class "Default")
      (node (ref "IC12") (pin "19") (pinfunction "ENCA_DCIN_CFG5_19") (pintype "bidirectional"))
      (node (ref "U4") (pin "1") (pinfunction "QB_1") (pintype "output"))
    )
    (net (code "144") (name "Net-(IC12-ENCB_DCEN_CFG4)") (class "Default")
      (node (ref "IC12") (pin "18") (pinfunction "ENCB_DCEN_CFG4_18") (pintype "bidirectional"))
      (node (ref "U4") (pin "2") (pinfunction "QC_2") (pintype "output"))
    )
    (net (code "145") (name "Net-(IC12-OA1)") (class "Default")
      (node (ref "IC12") (pin "34") (pinfunction "OA1_34") (pintype "bidirectional"))
      (node (ref "X17") (pin "2") (pinfunction "S_2") (pintype "passive"))
    )
    (net (code "146") (name "Net-(IC12-OA2)") (class "Default")
      (node (ref "IC12") (pin "32") (pinfunction "OA2_32") (pintype "bidirectional"))
      (node (ref "X17") (pin "3") (pinfunction "S_3") (pintype "passive"))
    )
    (net (code "147") (name "Net-(IC12-OB1)") (class "Default")
      (node (ref "IC12") (pin "13") (pinfunction "OB1_13") (pintype "bidirectional"))
      (node (ref "X17") (pin "1") (pinfunction "S_1") (pintype "passive"))
    )
    (net (code "148") (name "Net-(IC12-OB2)") (class "Default")
      (node (ref "IC12") (pin "15") (pinfunction "OB2_15") (pintype "bidirectional"))
      (node (ref "X17") (pin "4") (pinfunction "S_4") (pintype "passive"))
    )
    (net (code "149") (name "Net-(IC12-SCK_CFG2)") (class "Default")
      (node (ref "IC12") (pin "3") (pinfunction "SCK_CFG2_3") (pintype "bidirectional"))
      (node (ref "IC13") (pin "4") (pinfunction "O_4") (pintype "output"))
    )
    (net (code "150") (name "Net-(IC12-SDI_NAI_CFG1)") (class "Default")
      (node (ref "IC12") (pin "4") (pinfunction "SDI_NAI_CFG1_4") (pintype "bidirectional"))
      (node (ref "IC14") (pin "4") (pinfunction "O_4") (pintype "output"))
    )
    (net (code "151") (name "Net-(IC12-SDO_NAO_CFG0)") (class "Default")
      (node (ref "IC12") (pin "5") (pinfunction "SDO_NAO_CFG0_5") (pintype "bidirectional"))
      (node (ref "U4") (pin "3") (pinfunction "QD_3") (pintype "output"))
    )
    (net (code "152") (name "Net-(IC12-VCC)") (class "Default")
      (node (ref "C74") (pin "1") (pinfunction "1_1") (pintype "passive"))
      (node (ref "IC12") (pin "26") (pinfunction "VCC_26") (pintype "bidirectional"))
      (node (ref "R71") (pin "2") (pinfunction "2_2") (pintype "passive"))
    )
    (net (code "153") (name "Net-(IC12-VCP)") (class "Default")
      (node (ref "C66") (pin "1") (pinfunction "1_1") (pintype "passive"))
      (node (ref "IC12") (pin "29") (pinfunction "VCP_29") (pintype "bidirectional"))
    )
    (net (code "154") (name "Net-(IC13A-I)") (class "Default")
      (node (ref "IC13") (pin "2") (pinfunction "I_2") (pintype "input"))
      (node (ref "U4") (pin "4") (pinfunction "QE_4") (pintype "output"))
    )
    (net (code "155") (name "Net-(IC13A-OE)") (class "Default")
      (node (ref "IC13") (pin "1") (pinfunction "OE_1") (pintype "input"))
      (node (ref "U4") (pin "5") (pinfunction "QF_5") (pintype "output"))
    )
    (net (code "156") (name "Net-(IC14A-I)") (class "Default")
      (node (ref "IC14") (pin "2") (pinfunction "I_2") (pintype "input"))
      (node (ref "U4") (pin "6") (pinfunction "QG_6") (pintype "output"))
    )
    (net (code "157") (name "Net-(IC14A-OE)") (class "Default")
      (node (ref "IC14") (pin "1") (pinfunction "OE_1") (pintype "input"))
      (node (ref "U4") (pin "7") (pinfunction "QH_7") (pintype "output"))
    )
    (net (code "158") (name "Net-(IC15-5VOUT)") (class "Default")
      (node (ref "C68") (pin "2") (pinfunction "2_2") (pintype "passive"))
      (node (ref "IC15") (pin "25") (pinfunction "5VOUT_25") (pintype "bidirectional"))
      (node (ref "R52") (pin "1") (pinfunction "1_1") (pintype "passive"))
    )
    (net (code "159") (name "Net-(IC15-AIN_IREF)") (class "Default")
      (node (ref "C36") (pin "1") (pinfunction "1_1") (pintype "passive"))
      (node (ref "IC15") (pin "23") (pinfunction "AIN_IREF_23") (pintype "bidirectional"))
      (node (ref "R50") (pin "1") (pinfunction "1_1") (pintype "passive"))
    )
    (net (code "160") (name "Net-(IC15-BRA)") (class "Default")
      (node (ref "IC15") (pin "33") (pinfunction "BRA_33") (pintype "bidirectional"))
      (node (ref "R10") (pin "2") (pinfunction "2_2") (pintype "passive"))
    )
    (net (code "161") (name "Net-(IC15-BRB)") (class "Default")
      (node (ref "IC15") (pin "14") (pinfunction "BRB_14") (pintype "bidirectional"))
      (node (ref "R9") (pin "2") (pinfunction "2_2") (pintype "passive"))
    )
    (net (code "162") (name "Net-(IC15-CPI)") (class "Default")
      (node (ref "C9") (pin "1") (pinfunction "1_1") (pintype "passive"))
      (node (ref "IC15") (pin "28") (pinfunction "CPI_28") (pintype "bidirectional"))
    )
    (net (code "163") (name "Net-(IC15-CPO)") (class "Default")
      (node (ref "C9") (pin "2") (pinfunction "2_2") (pintype "passive"))
      (node (ref "IC15") (pin "27") (pinfunction "CPO_27") (pintype "bidirectional"))
    )
    (net (code "164") (name "Net-(IC15-DRV_ENN_CFG6)") (class "Default")
      (node (ref "IC15") (pin "22") (pinfunction "DRV_ENN_CFG6_22") (pintype "bidirectional"))
      (node (ref "U5") (pin "15") (pinfunction "QA_15") (pintype "output"))
    )
    (net (code "165") (name "Net-(IC15-ENCA_DCIN_CFG5)") (class "Default")
      (node (ref "IC15") (pin "19") (pinfunction "ENCA_DCIN_CFG5_19") (pintype "bidirectional"))
      (node (ref "U5") (pin "1") (pinfunction "QB_1") (pintype "output"))
    )
    (net (code "166") (name "Net-(IC15-ENCB_DCEN_CFG4)") (class "Default")
      (node (ref "IC15") (pin "18") (pinfunction "ENCB_DCEN_CFG4_18") (pintype "bidirectional"))
      (node (ref "U5") (pin "2") (pinfunction "QC_2") (pintype "output"))
    )
    (net (code "167") (name "Net-(IC15-OA1)") (class "Default")
      (node (ref "IC15") (pin "34") (pinfunction "OA1_34") (pintype "bidirectional"))
      (node (ref "X18") (pin "2") (pinfunction "S_2") (pintype "passive"))
    )
    (net (code "168") (name "Net-(IC15-OA2)") (class "Default")
      (node (ref "IC15") (pin "32") (pinfunction "OA2_32") (pintype "bidirectional"))
      (node (ref "X18") (pin "3") (pinfunction "S_3") (pintype "passive"))
    )
    (net (code "169") (name "Net-(IC15-OB1)") (class "Default")
      (node (ref "IC15") (pin "13") (pinfunction "OB1_13") (pintype "bidirectional"))
      (node (ref "X18") (pin "1") (pinfunction "S_1") (pintype "passive"))
    )
    (net (code "170") (name "Net-(IC15-OB2)") (class "Default")
      (node (ref "IC15") (pin "15") (pinfunction "OB2_15") (pintype "bidirectional"))
      (node (ref "X18") (pin "4") (pinfunction "S_4") (pintype "passive"))
    )
    (net (code "171") (name "Net-(IC15-SCK_CFG2)") (class "Default")
      (node (ref "IC15") (pin "3") (pinfunction "SCK_CFG2_3") (pintype "bidirectional"))
      (node (ref "IC16") (pin "4") (pinfunction "O_4") (pintype "output"))
    )
    (net (code "172") (name "Net-(IC15-SDI_NAI_CFG1)") (class "Default")
      (node (ref "IC15") (pin "4") (pinfunction "SDI_NAI_CFG1_4") (pintype "bidirectional"))
      (node (ref "IC17") (pin "4") (pinfunction "O_4") (pintype "output"))
    )
    (net (code "173") (name "Net-(IC15-SDO_NAO_CFG0)") (class "Default")
      (node (ref "IC15") (pin "5") (pinfunction "SDO_NAO_CFG0_5") (pintype "bidirectional"))
      (node (ref "U5") (pin "3") (pinfunction "QD_3") (pintype "output"))
    )
    (net (code "174") (name "Net-(IC15-VCC)") (class "Default")
      (node (ref "C70") (pin "1") (pinfunction "1_1") (pintype "passive"))
      (node (ref "IC15") (pin "26") (pinfunction "VCC_26") (pintype "bidirectional"))
      (node (ref "R52") (pin "2") (pinfunction "2_2") (pintype "passive"))
    )
    (net (code "175") (name "Net-(IC15-VCP)") (class "Default")
      (node (ref "C69") (pin "1") (pinfunction "1_1") (pintype "passive"))
      (node (ref "IC15") (pin "29") (pinfunction "VCP_29") (pintype "bidirectional"))
    )
    (net (code "176") (name "Net-(IC16A-I)") (class "Default")
      (node (ref "IC16") (pin "2") (pinfunction "I_2") (pintype "input"))
      (node (ref "U5") (pin "4") (pinfunction "QE_4") (pintype "output"))
    )
    (net (code "177") (name "Net-(IC16A-OE)") (class "Default")
      (node (ref "IC16") (pin "1") (pinfunction "OE_1") (pintype "input"))
      (node (ref "U5") (pin "5") (pinfunction "QF_5") (pintype "output"))
    )
    (net (code "178") (name "Net-(IC17A-I)") (class "Default")
      (node (ref "IC17") (pin "2") (pinfunction "I_2") (pintype "input"))
      (node (ref "U5") (pin "6") (pinfunction "QG_6") (pintype "output"))
    )
    (net (code "179") (name "Net-(IC17A-OE)") (class "Default")
      (node (ref "IC17") (pin "1") (pinfunction "OE_1") (pintype "input"))
      (node (ref "U5") (pin "7") (pinfunction "QH_7") (pintype "output"))
    )
    (net (code "180") (name "Net-(LED1-PadA)") (class "Default")
      (node (ref "LED1") (pin "A") (pinfunction "A_A") (pintype "passive"))
      (node (ref "R14") (pin "1") (pinfunction "1_1") (pintype "passive"))
    )
    (net (code "181") (name "Net-(LED2-PadA)") (class "Default")
      (node (ref "LED2") (pin "A") (pinfunction "A_A") (pintype "passive"))
      (node (ref "R16") (pin "1") (pinfunction "1_1") (pintype "passive"))
    )
    (net (code "182") (name "Net-(LED3-PadA)") (class "Default")
      (node (ref "LED3") (pin "A") (pinfunction "A_A") (pintype "passive"))
      (node (ref "R15") (pin "1") (pinfunction "1_1") (pintype "passive"))
    )
    (net (code "183") (name "Net-(LED4-PadA)") (class "Default")
      (node (ref "LED4") (pin "A") (pinfunction "A_A") (pintype "passive"))
      (node (ref "R11") (pin "1") (pinfunction "1_1") (pintype "passive"))
    )
    (net (code "184") (name "Net-(LED5-PadA)") (class "Default")
      (node (ref "LED5") (pin "A") (pinfunction "A_A") (pintype "passive"))
      (node (ref "R19") (pin "1") (pinfunction "1_1") (pintype "passive"))
    )
    (net (code "185") (name "Net-(LED6-PadA)") (class "Default")
      (node (ref "LED6") (pin "A") (pinfunction "A_A") (pintype "passive"))
      (node (ref "R20") (pin "1") (pinfunction "1_1") (pintype "passive"))
    )
    (net (code "186") (name "Net-(LED7-PadA)") (class "Default")
      (node (ref "LED7") (pin "A") (pinfunction "A_A") (pintype "passive"))
      (node (ref "R21") (pin "1") (pinfunction "1_1") (pintype "passive"))
    )
    (net (code "187") (name "Net-(LED8-PadC)") (class "Default")
      (node (ref "LED8") (pin "C") (pinfunction "C_C") (pintype "passive"))
      (node (ref "R45") (pin "2") (pinfunction "2_2") (pintype "passive"))
    )
    (net (code "188") (name "Net-(LED9-PadA)") (class "Default")
      (node (ref "LED9") (pin "A") (pinfunction "A_A") (pintype "passive"))
      (node (ref "R25") (pin "1") (pinfunction "1_1") (pintype "passive"))
    )
    (net (code "189") (name "Net-(Q4-C)") (class "Default")
      (node (ref "LED6") (pin "C") (pinfunction "C_C") (pintype "passive"))
      (node (ref "Q4") (pin "3") (pinfunction "C_3") (pintype "passive"))
      (node (ref "X5") (pin "2") (pinfunction "S_2") (pintype "passive"))
    )
    (net (code "190") (name "Net-(Q5-C)") (class "Default")
      (node (ref "LED7") (pin "C") (pinfunction "C_C") (pintype "passive"))
      (node (ref "Q5") (pin "3") (pinfunction "C_3") (pintype "passive"))
      (node (ref "X6") (pin "2") (pinfunction "S_2") (pintype "passive"))
    )
    (net (code "191") (name "Net-(Q6-C)") (class "Default")
      (node (ref "LED9") (pin "C") (pinfunction "C_C") (pintype "passive"))
      (node (ref "Q6") (pin "3") (pinfunction "C_3") (pintype "passive"))
      (node (ref "X9") (pin "2") (pinfunction "S_2") (pintype "passive"))
    )
    (net (code "192") (name "Net-(Q7-C)") (class "Default")
      (node (ref "LED5") (pin "C") (pinfunction "C_C") (pintype "passive"))
      (node (ref "Q7") (pin "3") (pinfunction "C_3") (pintype "passive"))
      (node (ref "X4") (pin "2") (pinfunction "S_2") (pintype "passive"))
    )
    (net (code "193") (name "Net-(U6-BOOT)") (class "Default")
      (node (ref "C50") (pin "1") (pinfunction "1_1") (pintype "passive"))
      (node (ref "U6") (pin "2") (pinfunction "BOOT_2") (pintype "input"))
    )
    (net (code "194") (name "Net-(U6-COMP)") (class "Default")
      (node (ref "C51") (pin "1") (pinfunction "1_1") (pintype "passive"))
      (node (ref "U6") (pin "8") (pinfunction "COMP_8") (pintype "bidirectional"))
    )
    (net (code "195") (name "Net-(U6-FB)") (class "Default")
      (node (ref "R12") (pin "2") (pinfunction "2_2") (pintype "passive"))
      (node (ref "R22") (pin "1") (pinfunction "1_1") (pintype "passive"))
      (node (ref "U6") (pin "7") (pinfunction "FB_7") (pintype "input"))
    )
    (net (code "196") (name "Net-(U6-SS)") (class "Default")
      (node (ref "C49") (pin "1") (pinfunction "1_1") (pintype "passive"))
      (node (ref "U6") (pin "10") (pinfunction "SS_10") (pintype "bidirectional"))
    )
    (net (code "197") (name "Net-(U6-SW)") (class "Default")
      (node (ref "C50") (pin "2") (pinfunction "2_2") (pintype "passive"))
      (node (ref "D6") (pin "C") (pinfunction "C_C") (pintype "passive"))
      (node (ref "L1") (pin "P$2") (pinfunction "P$2_P$2") (pintype "passive"))
      (node (ref "U6") (pin "5") (pinfunction "SW_5") (pintype "power_in"))
    )
    (net (code "198") (name "Net-(U10-BOOT)") (class "Default")
      (node (ref "C55") (pin "1") (pinfunction "1_1") (pintype "passive"))
      (node (ref "U10") (pin "2") (pinfunction "BOOT_2") (pintype "input"))
    )
    (net (code "199") (name "Net-(U10-COMP)") (class "Default")
      (node (ref "C56") (pin "1") (pinfunction "1_1") (pintype "passive"))
      (node (ref "U10") (pin "8") (pinfunction "COMP_8") (pintype "bidirectional"))
    )
    (net (code "200") (name "Net-(U10-FB)") (class "Default")
      (node (ref "R42") (pin "2") (pinfunction "2_2") (pintype "passive"))
      (node (ref "R43") (pin "1") (pinfunction "1_1") (pintype "passive"))
      (node (ref "U10") (pin "7") (pinfunction "FB_7") (pintype "input"))
    )
    (net (code "201") (name "Net-(U10-SS)") (class "Default")
      (node (ref "C54") (pin "1") (pinfunction "1_1") (pintype "passive"))
      (node (ref "U10") (pin "10") (pinfunction "SS_10") (pintype "bidirectional"))
    )
    (net (code "202") (name "Net-(U10-SW)") (class "Default")
      (node (ref "C55") (pin "2") (pinfunction "2_2") (pintype "passive"))
      (node (ref "D4") (pin "C") (pinfunction "C_C") (pintype "passive"))
      (node (ref "L2") (pin "P$2") (pinfunction "P$2_P$2") (pintype "passive"))
      (node (ref "U10") (pin "5") (pinfunction "SW_5") (pintype "power_in"))
    )
    (net (code "203") (name "Net-(X3B-1)") (class "Default")
      (node (ref "C59") (pin "1") (pinfunction "1_1") (pintype "passive"))
      (node (ref "D1") (pin "A") (pinfunction "A_A") (pintype "passive"))
      (node (ref "LED3") (pin "C") (pinfunction "C_C") (pintype "passive"))
      (node (ref "Q3") (pin "5") (pinfunction "D_5") (pintype "passive"))
      (node (ref "Q3") (pin "6") (pinfunction "D_6") (pintype "passive"))
      (node (ref "Q3") (pin "7") (pinfunction "D_7") (pintype "passive"))
      (node (ref "Q3") (pin "8") (pinfunction "D_8") (pintype "passive"))
      (node (ref "Q3") (pin "TH") (pinfunction "D_TH") (pintype "passive"))
      (node (ref "R55") (pin "1") (pinfunction "1_1") (pintype "passive"))
      (node (ref "X3") (pin "2") (pinfunction "1_2") (pintype "passive"))
    )
    (net (code "204") (name "Net-(X7B-S)") (class "Default")
      (node (ref "R17") (pin "1") (pinfunction "1_1") (pintype "passive"))
      (node (ref "R39") (pin "1") (pinfunction "1_1") (pintype "passive"))
      (node (ref "X7") (pin "2") (pinfunction "S_2") (pintype "passive"))
    )
    (net (code "205") (name "Net-(X8B-S)") (class "Default")
      (node (ref "R13") (pin "1") (pinfunction "1_1") (pintype "passive"))
      (node (ref "R38") (pin "1") (pinfunction "1_1") (pintype "passive"))
      (node (ref "X8") (pin "2") (pinfunction "S_2") (pintype "passive"))
    )
    (net (code "206") (name "Net-(X11B-S)") (class "Default")
      (node (ref "R18") (pin "1") (pinfunction "1_1") (pintype "passive"))
      (node (ref "R40") (pin "1") (pinfunction "1_1") (pintype "passive"))
      (node (ref "X11") (pin "2") (pinfunction "S_2") (pintype "passive"))
    )
    (net (code "207") (name "Net-(X20C-1)") (class "Default")
      (node (ref "C58") (pin "1") (pinfunction "1_1") (pintype "passive"))
      (node (ref "D2") (pin "A") (pinfunction "A_A") (pintype "passive"))
      (node (ref "LED2") (pin "C") (pinfunction "C_C") (pintype "passive"))
      (node (ref "Q1") (pin "5") (pinfunction "D_5") (pintype "passive"))
      (node (ref "Q1") (pin "6") (pinfunction "D_6") (pintype "passive"))
      (node (ref "Q1") (pin "7") (pinfunction "D_7") (pintype "passive"))
      (node (ref "Q1") (pin "8") (pinfunction "D_8") (pintype "passive"))
      (node (ref "Q1") (pin "TH") (pinfunction "D_TH") (pintype "passive"))
      (node (ref "R56") (pin "1") (pinfunction "1_1") (pintype "passive"))
      (node (ref "X20") (pin "3") (pinfunction "1_3") (pintype "passive"))
      (node (ref "X20") (pin "4") (pinfunction "1_4") (pintype "passive"))
    )
    (net (code "208") (name "Net-(X21B-1)") (class "Default")
      (node (ref "C57") (pin "1") (pinfunction "1_1") (pintype "passive"))
      (node (ref "D3") (pin "A") (pinfunction "A_A") (pintype "passive"))
      (node (ref "LED1") (pin "C") (pinfunction "C_C") (pintype "passive"))
      (node (ref "Q2") (pin "5") (pinfunction "D_5") (pintype "passive"))
      (node (ref "Q2") (pin "6") (pinfunction "D_6") (pintype "passive"))
      (node (ref "Q2") (pin "7") (pinfunction "D_7") (pintype "passive"))
      (node (ref "Q2") (pin "8") (pinfunction "D_8") (pintype "passive"))
      (node (ref "Q2") (pin "TH") (pinfunction "D_TH") (pintype "passive"))
      (node (ref "R57") (pin "1") (pinfunction "1_1") (pintype "passive"))
      (node (ref "X21") (pin "2") (pinfunction "1_2") (pintype "passive"))
    )
    (net (code "209") (name "unconnected-(IC1-CSN_CFG3-Pad2)") (class "Default")
      (node (ref "IC1") (pin "2") (pinfunction "CSN_CFG3_2") (pintype "bidirectional"))
    )
    (net (code "210") (name "unconnected-(IC1-ENCN_DCO-Pad17)") (class "Default")
      (node (ref "IC1") (pin "17") (pinfunction "ENCN_DCO_17") (pintype "bidirectional"))
    )
    (net (code "211") (name "unconnected-(IC1-SD_MODE-Pad9)") (class "Default")
      (node (ref "IC1") (pin "9") (pinfunction "SD_MODE_9") (pintype "bidirectional"))
    )
    (net (code "212") (name "unconnected-(IC1-SWP_DIAG1-Pad21)") (class "Default")
      (node (ref "IC1") (pin "21") (pinfunction "SWP_DIAG1_21") (pintype "bidirectional"))
    )
    (net (code "213") (name "unconnected-(IC2-CSN_CFG3-Pad2)") (class "Default")
      (node (ref "IC2") (pin "2") (pinfunction "CSN_CFG3_2") (pintype "bidirectional"))
    )
    (net (code "214") (name "unconnected-(IC2-ENCN_DCO-Pad17)") (class "Default")
      (node (ref "IC2") (pin "17") (pinfunction "ENCN_DCO_17") (pintype "bidirectional"))
    )
    (net (code "215") (name "unconnected-(IC2-SD_MODE-Pad9)") (class "Default")
      (node (ref "IC2") (pin "9") (pinfunction "SD_MODE_9") (pintype "bidirectional"))
    )
    (net (code "216") (name "unconnected-(IC2-SWP_DIAG1-Pad21)") (class "Default")
      (node (ref "IC2") (pin "21") (pinfunction "SWP_DIAG1_21") (pintype "bidirectional"))
    )
    (net (code "217") (name "unconnected-(IC5-CSN_CFG3-Pad2)") (class "Default")
      (node (ref "IC5") (pin "2") (pinfunction "CSN_CFG3_2") (pintype "bidirectional"))
    )
    (net (code "218") (name "unconnected-(IC5-ENCN_DCO-Pad17)") (class "Default")
      (node (ref "IC5") (pin "17") (pinfunction "ENCN_DCO_17") (pintype "bidirectional"))
    )
    (net (code "219") (name "unconnected-(IC5-SD_MODE-Pad9)") (class "Default")
      (node (ref "IC5") (pin "9") (pinfunction "SD_MODE_9") (pintype "bidirectional"))
    )
    (net (code "220") (name "unconnected-(IC5-SWP_DIAG1-Pad21)") (class "Default")
      (node (ref "IC5") (pin "21") (pinfunction "SWP_DIAG1_21") (pintype "bidirectional"))
    )
    (net (code "221") (name "unconnected-(IC12-CSN_CFG3-Pad2)") (class "Default")
      (node (ref "IC12") (pin "2") (pinfunction "CSN_CFG3_2") (pintype "bidirectional"))
    )
    (net (code "222") (name "unconnected-(IC12-ENCN_DCO-Pad17)") (class "Default")
      (node (ref "IC12") (pin "17") (pinfunction "ENCN_DCO_17") (pintype "bidirectional"))
    )
    (net (code "223") (name "unconnected-(IC12-SD_MODE-Pad9)") (class "Default")
      (node (ref "IC12") (pin "9") (pinfunction "SD_MODE_9") (pintype "bidirectional"))
    )
    (net (code "224") (name "unconnected-(IC12-SWP_DIAG1-Pad21)") (class "Default")
      (node (ref "IC12") (pin "21") (pinfunction "SWP_DIAG1_21") (pintype "bidirectional"))
    )
    (net (code "225") (name "unconnected-(IC15-CSN_CFG3-Pad2)") (class "Default")
      (node (ref "IC15") (pin "2") (pinfunction "CSN_CFG3_2") (pintype "bidirectional"))
    )
    (net (code "226") (name "unconnected-(IC15-ENCN_DCO-Pad17)") (class "Default")
      (node (ref "IC15") (pin "17") (pinfunction "ENCN_DCO_17") (pintype "bidirectional"))
    )
    (net (code "227") (name "unconnected-(IC15-SD_MODE-Pad9)") (class "Default")
      (node (ref "IC15") (pin "9") (pinfunction "SD_MODE_9") (pintype "bidirectional"))
    )
    (net (code "228") (name "unconnected-(IC15-SWP_DIAG1-Pad21)") (class "Default")
      (node (ref "IC15") (pin "21") (pinfunction "SWP_DIAG1_21") (pintype "bidirectional"))
    )
    (net (code "229") (name "unconnected-(P8-Pad3)") (class "Default")
      (node (ref "P8") (pin "3") (pinfunction "3_3") (pintype "passive"))
    )
    (net (code "230") (name "unconnected-(P8-Pad4)") (class "Default")
      (node (ref "P8") (pin "4") (pinfunction "4_4") (pintype "passive"))
    )
    (net (code "231") (name "unconnected-(P8-Pad5)") (class "Default")
      (node (ref "P8") (pin "5") (pinfunction "5_5") (pintype "passive"))
    )
    (net (code "232") (name "unconnected-(P8-Pad6)") (class "Default")
      (node (ref "P8") (pin "6") (pinfunction "6_6") (pintype "passive"))
    )
    (net (code "233") (name "unconnected-(P8-Pad7)") (class "Default")
      (node (ref "P8") (pin "7") (pinfunction "7_7") (pintype "passive"))
    )
    (net (code "234") (name "unconnected-(P8-Pad20)") (class "Default")
      (node (ref "P8") (pin "20") (pinfunction "20_20") (pintype "passive"))
    )
    (net (code "235") (name "unconnected-(P8-Pad21)") (class "Default")
      (node (ref "P8") (pin "21") (pinfunction "21_21") (pintype "passive"))
    )
    (net (code "236") (name "unconnected-(P8-Pad22)") (class "Default")
      (node (ref "P8") (pin "22") (pinfunction "22_22") (pintype "passive"))
    )
    (net (code "237") (name "unconnected-(P8-Pad23)") (class "Default")
      (node (ref "P8") (pin "23") (pinfunction "23_23") (pintype "passive"))
    )
    (net (code "238") (name "unconnected-(P8-Pad24)") (class "Default")
      (node (ref "P8") (pin "24") (pinfunction "24_24") (pintype "passive"))
    )
    (net (code "239") (name "unconnected-(P8-Pad25)") (class "Default")
      (node (ref "P8") (pin "25") (pinfunction "25_25") (pintype "passive"))
    )
    (net (code "240") (name "unconnected-(P8-Pad27)") (class "Default")
      (node (ref "P8") (pin "27") (pinfunction "27_27") (pintype "passive"))
    )
    (net (code "241") (name "unconnected-(P8-Pad28)") (class "Default")
      (node (ref "P8") (pin "28") (pinfunction "28_28") (pintype "passive"))
    )
    (net (code "242") (name "unconnected-(P8-Pad29)") (class "Default")
      (node (ref "P8") (pin "29") (pinfunction "29_29") (pintype "passive"))
    )
    (net (code "243") (name "unconnected-(P8-Pad30)") (class "Default")
      (node (ref "P8") (pin "30") (pinfunction "30_30") (pintype "passive"))
    )
    (net (code "244") (name "unconnected-(P8-Pad31)") (class "Default")
      (node (ref "P8") (pin "31") (pinfunction "31_31") (pintype "passive"))
    )
    (net (code "245") (name "unconnected-(P8-Pad32)") (class "Default")
      (node (ref "P8") (pin "32") (pinfunction "32_32") (pintype "passive"))
    )
    (net (code "246") (name "unconnected-(P8-Pad33)") (class "Default")
      (node (ref "P8") (pin "33") (pinfunction "33_33") (pintype "passive"))
    )
    (net (code "247") (name "unconnected-(P8-Pad34)") (class "Default")
      (node (ref "P8") (pin "34") (pinfunction "34_34") (pintype "passive"))
    )
    (net (code "248") (name "unconnected-(P8-Pad35)") (class "Default")
      (node (ref "P8") (pin "35") (pinfunction "35_35") (pintype "passive"))
    )
    (net (code "249") (name "unconnected-(P8-Pad36)") (class "Default")
      (node (ref "P8") (pin "36") (pinfunction "36_36") (pintype "passive"))
    )
    (net (code "250") (name "unconnected-(P8-Pad37)") (class "Default")
      (node (ref "P8") (pin "37") (pinfunction "37_37") (pintype "passive"))
    )
    (net (code "251") (name "unconnected-(P8-Pad38)") (class "Default")
      (node (ref "P8") (pin "38") (pinfunction "38_38") (pintype "passive"))
    )
    (net (code "252") (name "unconnected-(P8-Pad39)") (class "Default")
      (node (ref "P8") (pin "39") (pinfunction "39_39") (pintype "passive"))
    )
    (net (code "253") (name "unconnected-(P8-Pad40)") (class "Default")
      (node (ref "P8") (pin "40") (pinfunction "40_40") (pintype "passive"))
    )
    (net (code "254") (name "unconnected-(P8-Pad41)") (class "Default")
      (node (ref "P8") (pin "41") (pinfunction "41_41") (pintype "passive"))
    )
    (net (code "255") (name "unconnected-(P8-Pad42)") (class "Default")
      (node (ref "P8") (pin "42") (pinfunction "42_42") (pintype "passive"))
    )
    (net (code "256") (name "unconnected-(P8-Pad43)") (class "Default")
      (node (ref "P8") (pin "43") (pinfunction "43_43") (pintype "passive"))
    )
    (net (code "257") (name "unconnected-(P8-Pad44)") (class "Default")
      (node (ref "P8") (pin "44") (pinfunction "44_44") (pintype "passive"))
    )
    (net (code "258") (name "unconnected-(P8-Pad45)") (class "Default")
      (node (ref "P8") (pin "45") (pinfunction "45_45") (pintype "passive"))
    )
    (net (code "259") (name "unconnected-(P8-Pad46)") (class "Default")
      (node (ref "P8") (pin "46") (pinfunction "46_46") (pintype "passive"))
    )
    (net (code "260") (name "unconnected-(P9-Pad7)") (class "Default")
      (node (ref "P9") (pin "7") (pinfunction "7_7") (pintype "passive"))
    )
    (net (code "261") (name "unconnected-(P9-Pad8)") (class "Default")
      (node (ref "P9") (pin "8") (pinfunction "8_8") (pintype "passive"))
    )
    (net (code "262") (name "unconnected-(P9-Pad9)") (class "Default")
      (node (ref "P9") (pin "9") (pinfunction "9_9") (pintype "passive"))
    )
    (net (code "263") (name "unconnected-(P9-Pad10)") (class "Default")
      (node (ref "P9") (pin "10") (pinfunction "10_10") (pintype "passive"))
    )
    (net (code "264") (name "unconnected-(P9-Pad15)") (class "Default")
      (node (ref "P9") (pin "15") (pinfunction "15_15") (pintype "passive"))
    )
    (net (code "265") (name "unconnected-(P9-Pad17)") (class "Default")
      (node (ref "P9") (pin "17") (pinfunction "17_17") (pintype "passive"))
    )
    (net (code "266") (name "unconnected-(P9-Pad21)") (class "Default")
      (node (ref "P9") (pin "21") (pinfunction "21_21") (pintype "passive"))
    )
    (net (code "267") (name "unconnected-(P9-Pad26)") (class "Default")
      (node (ref "P9") (pin "26") (pinfunction "26_26") (pintype "passive"))
    )
    (net (code "268") (name "unconnected-(P9-Pad27)") (class "Default")
      (node (ref "P9") (pin "27") (pinfunction "27_27") (pintype "passive"))
    )
    (net (code "269") (name "unconnected-(P9-Pad29)") (class "Default")
      (node (ref "P9") (pin "29") (pinfunction "29_29") (pintype "passive"))
    )
    (net (code "270") (name "unconnected-(P9-Pad34)") (class "Default")
      (node (ref "P9") (pin "34") (pinfunction "34_34") (pintype "passive"))
    )
    (net (code "271") (name "unconnected-(P9-Pad37)") (class "Default")
      (node (ref "P9") (pin "37") (pinfunction "37_37") (pintype "passive"))
    )
    (net (code "272") (name "unconnected-(P9-Pad38)") (class "Default")
      (node (ref "P9") (pin "38") (pinfunction "38_38") (pintype "passive"))
    )
    (net (code "273") (name "unconnected-(P9-Pad39)") (class "Default")
      (node (ref "P9") (pin "39") (pinfunction "39_39") (pintype "passive"))
    )
    (net (code "274") (name "unconnected-(P9-Pad40)") (class "Default")
      (node (ref "P9") (pin "40") (pinfunction "40_40") (pintype "passive"))
    )
    (net (code "275") (name "unconnected-(U5-QH_2-Pad9)") (class "Default")
      (node (ref "U5") (pin "9") (pinfunction "QH_2_9") (pintype "output"))
    )
    (net (code "276") (name "unconnected-(U6-EN-Pad9)") (class "Default")
      (node (ref "U6") (pin "9") (pinfunction "EN_9") (pintype "input"))
    )
    (net (code "277") (name "unconnected-(U10-EN-Pad9)") (class "Default")
      (node (ref "U10") (pin "9") (pinfunction "EN_9") (pintype "input"))
    )
    (net (code "278") (name "unconnected-(U11-EXTCLK-Pad25)") (class "Default")
      (node (ref "U11") (pin "25") (pinfunction "EXTCLK_25") (pintype "input"))
    )
    (net (code "279") (name "unconnected-(U11-LED0-Pad6)") (class "Default")
      (node (ref "U11") (pin "6") (pinfunction "LED0_6") (pintype "output"))
    )
    (net (code "280") (name "unconnected-(U11-LED1-Pad7)") (class "Default")
      (node (ref "U11") (pin "7") (pinfunction "LED1_7") (pintype "output"))
    )
    (net (code "281") (name "unconnected-(U11-LED2-Pad8)") (class "Default")
      (node (ref "U11") (pin "8") (pinfunction "LED2_8") (pintype "output"))
    )
    (net (code "282") (name "unconnected-(U11-LED6-Pad12)") (class "Default")
      (node (ref "U11") (pin "12") (pinfunction "LED6_12") (pintype "output"))
    )
    (net (code "283") (name "unconnected-(U18-~{WC}-Pad7)") (class "Default")
      (node (ref "U18") (pin "7") (pinfunction "~{WC}_7") (pintype "no_connect"))
    )
    (net (code "284") (name "unconnected-(U19-NC-Pad16)") (class "Default")
      (node (ref "U19") (pin "16") (pinfunction "NC_16") (pintype "no_connect"))
    )
    (net (code "285") (name "unconnected-(U19-NC_2-Pad13)") (class "Default")
      (node (ref "U19") (pin "13") (pinfunction "NC_2_13") (pintype "no_connect"))
    )
  )
)
